# Out_current_sensor_UVW.net
KiCad netlist of a schematic drawn in Altium Designer
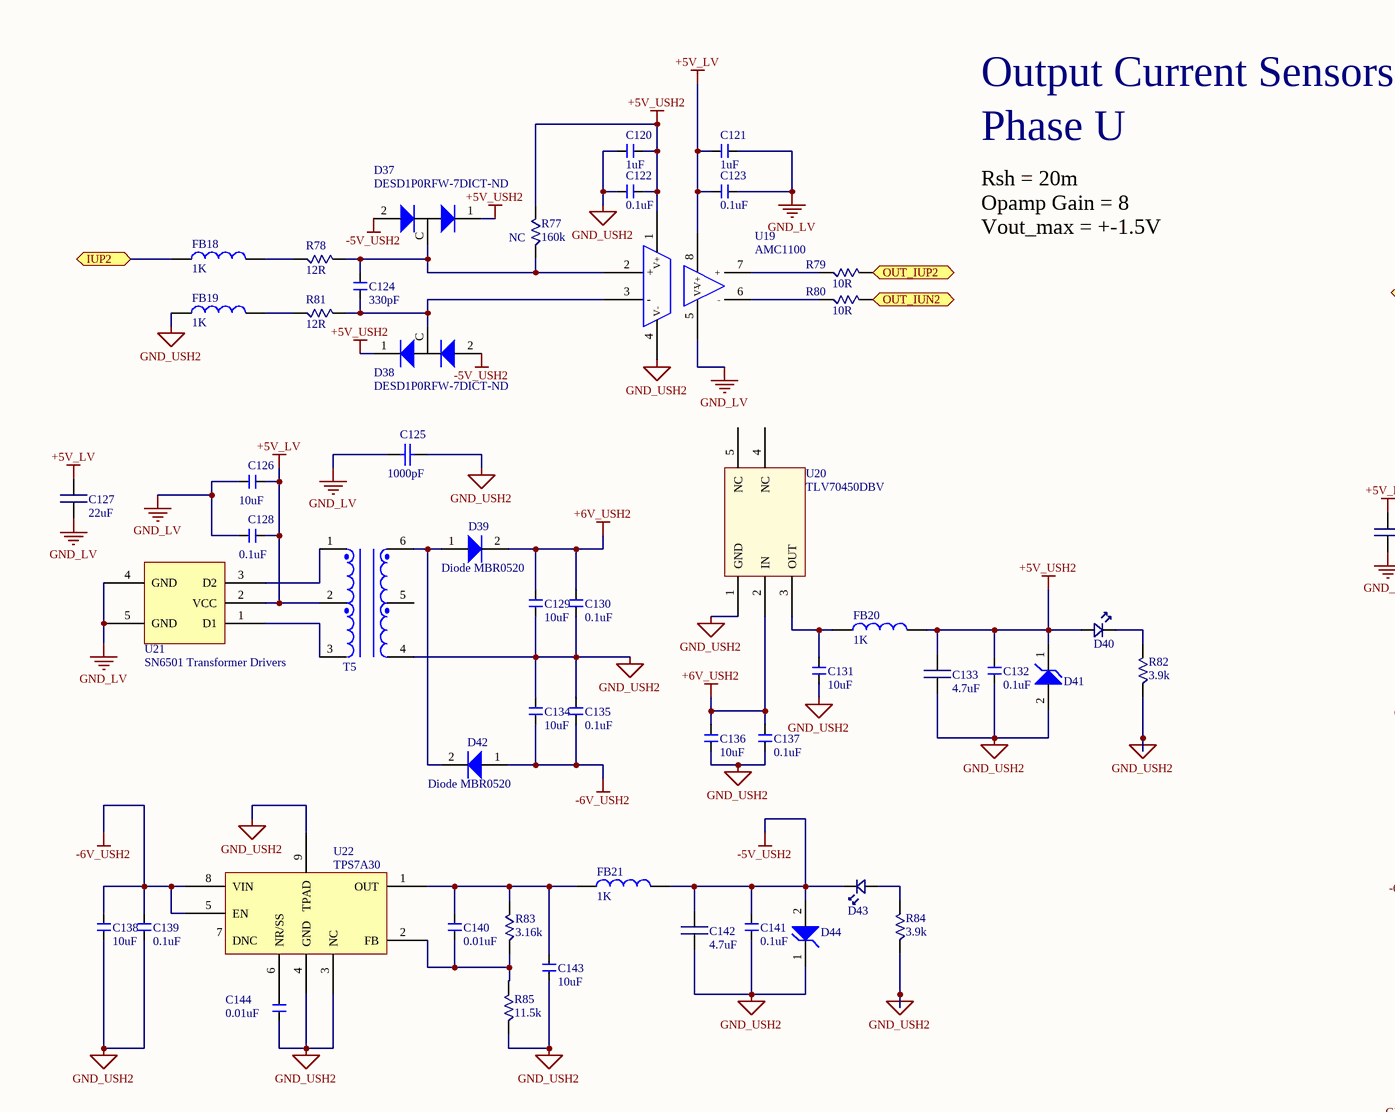
[diagram p0: Out_current_sensor_UVW.SchDoc, top left]
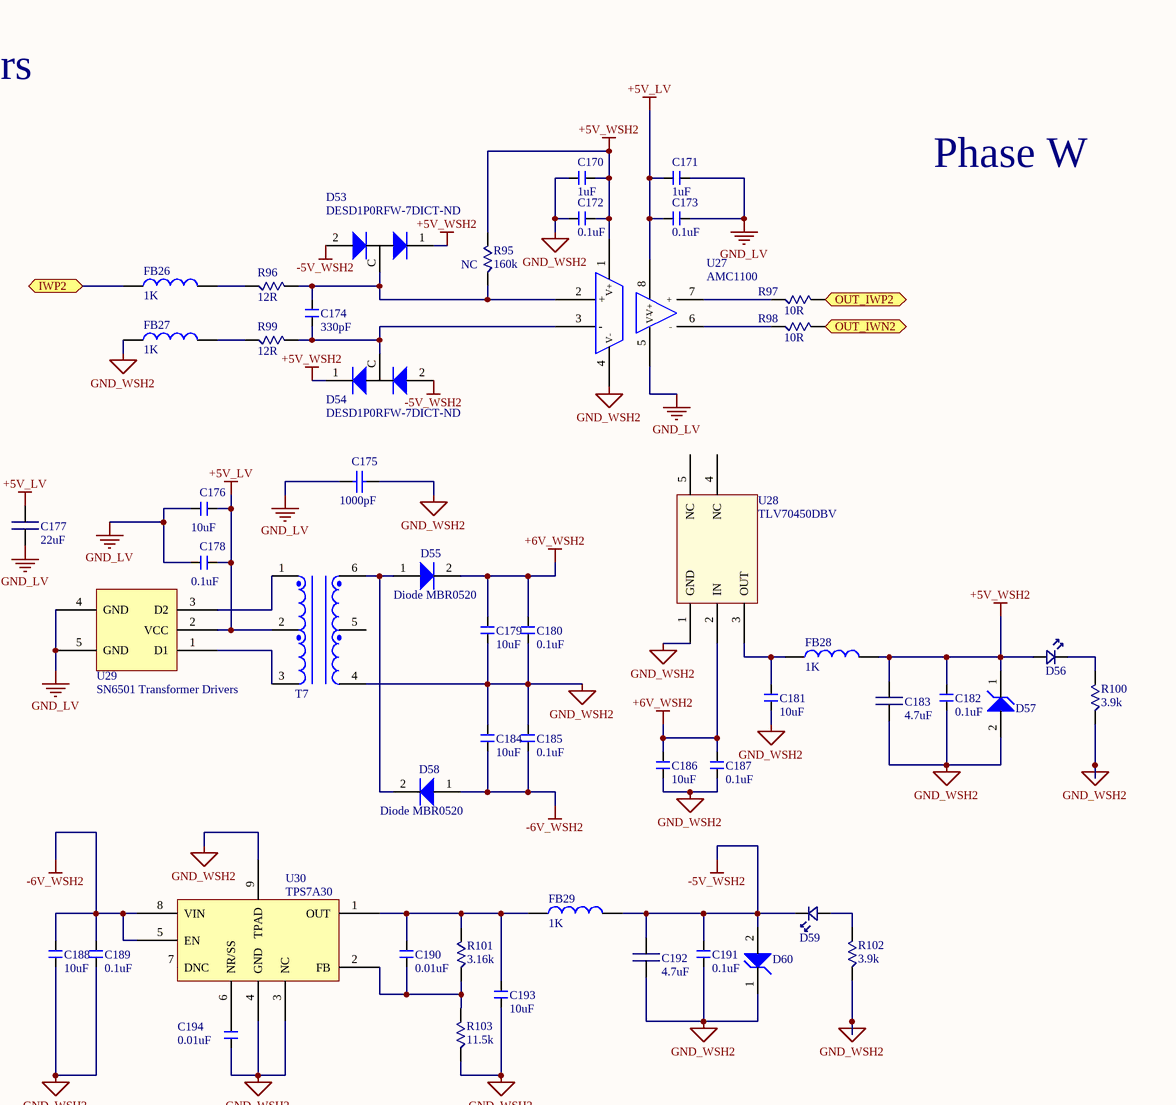
[diagram p1: Out_current_sensor_UVW.SchDoc, top right]
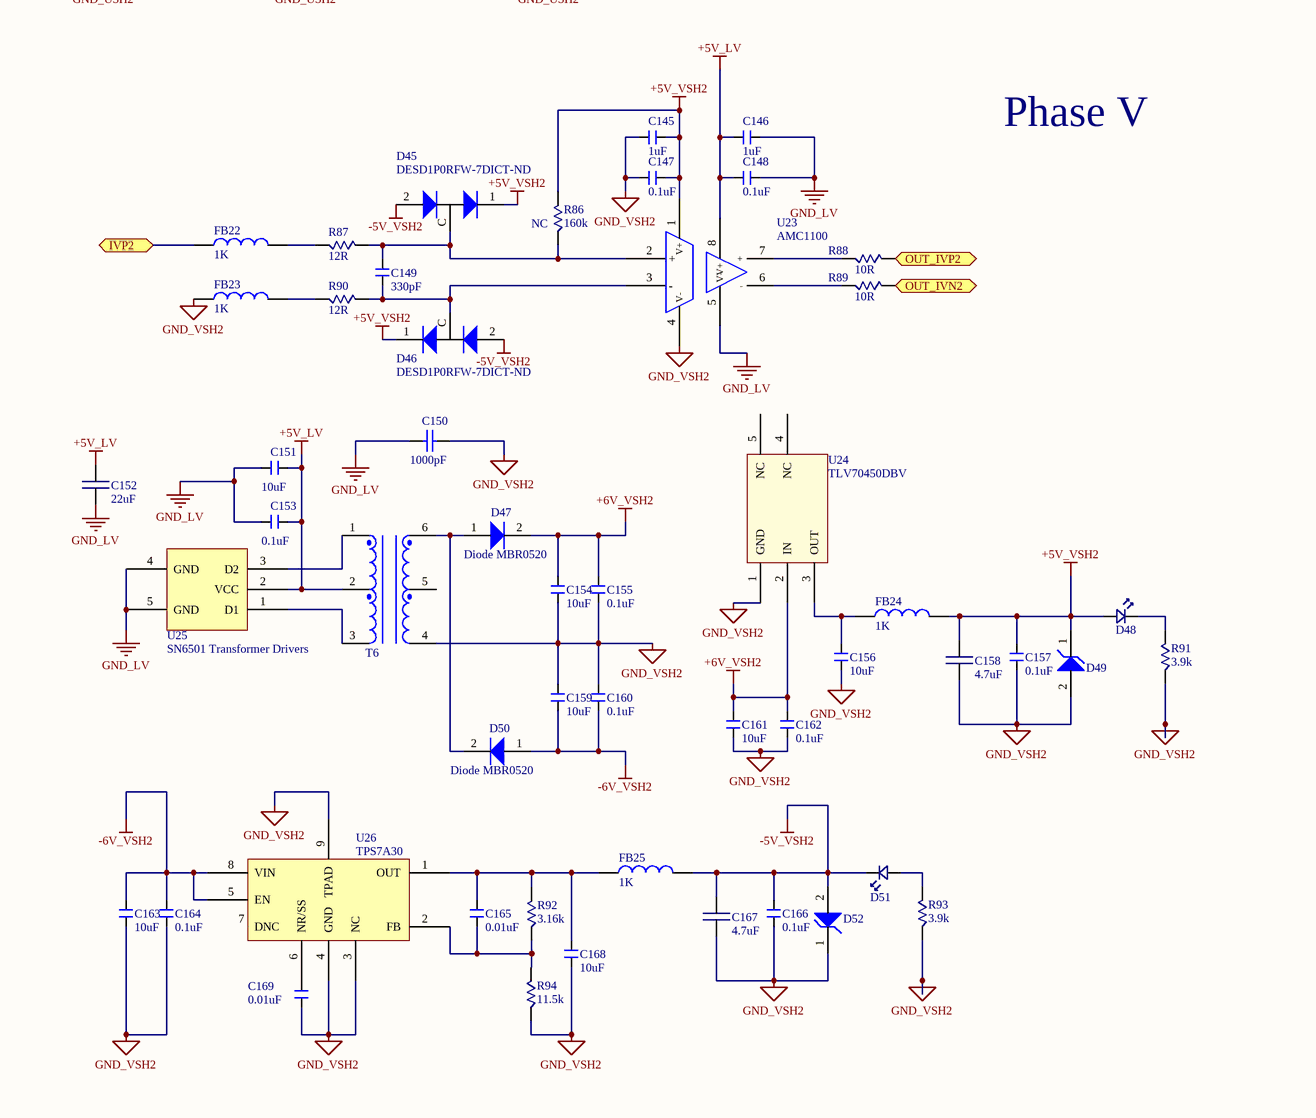
[diagram p2: Out_current_sensor_UVW.SchDoc, bottom left]

(export (version "E")
  (design (tool "Eeschema 10.0.6"))
  (components
    (comp (ref "C120")
      (value "1uF")
      (footprint "0603 (1608 Metric)")
      (description "CAP CER 1UF 50V X5R 0603")
      (fields (field (name "PART") "1276-1860-1-ND") (field (name "Comment") "Cap 0603_new"))
      (libsource (lib "Library_Microgrid") (part "Cap 0603_new"))
    )
    (comp (ref "C121")
      (value "1uF")
      (footprint "0603 (1608 Metric)")
      (description "CAP CER 1UF 50V X5R 0603")
      (fields (field (name "PART") "1276-1860-1-ND") (field (name "Comment") "Cap 0603_new"))
      (libsource (lib "Library_Microgrid") (part "Cap 0603_new"))
    )
    (comp (ref "C122")
      (value "0.1uF")
      (footprint "0603 (1608 Metric)")
      (description "CAP CER 0.1UF 50V Y5V 0603")
      (fields (field (name "PART") "311-1343-6-ND") (field (name "Comment") "Cap 0603_new"))
      (libsource (lib "Library_Microgrid") (part "Cap 0603_new"))
    )
    (comp (ref "C123")
      (value "0.1uF")
      (footprint "0603 (1608 Metric)")
      (description "CAP CER 0.1UF 50V Y5V 0603")
      (fields (field (name "PART") "311-1343-6-ND") (field (name "Comment") "Cap 0603_new"))
      (libsource (lib "Library_Microgrid") (part "Cap 0603_new"))
    )
    (comp (ref "C124")
      (value "330pF")
      (footprint "0603 (1608 Metric)")
      (description "CAP CER 330PF 50V C0G 0603")
      (fields (field (name "PART") "445-7033-2-ND") (field (name "Comment") "Cap 0603_new"))
      (libsource (lib "Library_Microgrid") (part "Cap 0603_new"))
    )
    (comp (ref "C125")
      (value "1000pF")
      (footprint "RAD-0.3")
      (description "CAP CER 1000PF 1KV Y5P RADIAL")
      (fields
        (field (name "PART") "1251PH-ND")
        (field (name "Comment") "Cap TH")
        (field (name "PUBLISHER") "Altium Limited")
      )
      (libsource (lib "Miscellaneous Devices") (part "Cap"))
    )
    (comp (ref "C126")
      (value "10uF")
      (footprint "0603 (1608 Metric)")
      (description "CAP CER 10UF 35V X5R 0805")
      (fields (field (name "PART") "490-10515-1-ND") (field (name "Comment") "Cap 0603_new"))
      (libsource (lib "Library_Microgrid") (part "Cap 0603_new"))
    )
    (comp (ref "C127")
      (value "22uF")
      (footprint "0805 (2012 metric)")
      (description "CAP CER 22UF 35V X5R 0805")
      (fields (field (name "PART") "445-14428-1-ND") (field (name "Comment") "Cap 0805"))
      (libsource (lib "Library_Microgrid") (part "Cap 0805"))
    )
    (comp (ref "C128")
      (value "0.1uF")
      (footprint "0603 (1608 Metric)")
      (description "CAP CER 0.1UF 50V Y5V 0603")
      (fields (field (name "PART") "311-1343-6-ND") (field (name "Comment") "Cap 0603_new"))
      (libsource (lib "Library_Microgrid") (part "Cap 0603_new"))
    )
    (comp (ref "C129")
      (value "10uF")
      (footprint "0603 (1608 Metric)")
      (description "CAP CER 10UF 35V X5R 0805")
      (fields (field (name "PART") "490-10515-1-ND") (field (name "Comment") "Cap 0603_new"))
      (libsource (lib "Library_Microgrid") (part "Cap 0603_new"))
    )
    (comp (ref "C130")
      (value "0.1uF")
      (footprint "0603 (1608 Metric)")
      (description "CAP CER 0.1UF 50V Y5V 0603")
      (fields (field (name "PART") "311-1343-6-ND") (field (name "Comment") "Cap 0603_new"))
      (libsource (lib "Library_Microgrid") (part "Cap 0603_new"))
    )
    (comp (ref "C131")
      (value "10uF")
      (footprint "0603 (1608 Metric)")
      (description "CAP CER 10UF 35V X5R 0805")
      (fields (field (name "PART") "490-10515-1-ND") (field (name "Comment") "Cap 0603_new"))
      (libsource (lib "Library_Microgrid") (part "Cap 0603_new"))
    )
    (comp (ref "C132")
      (value "0.1uF")
      (footprint "0603 (1608 Metric)")
      (description "CAP CER 0.1UF 50V Y5V 0603")
      (fields (field (name "PART") "311-1343-6-ND") (field (name "Comment") "Cap 0603_new"))
      (libsource (lib "Library_Microgrid") (part "Cap 0603_new"))
    )
    (comp (ref "C133")
      (value "4.7uF")
      (footprint "0805 (2012 metric)")
      (description "CAP CER 4.7UF 50V X5R 0805")
      (fields (field (name "PART") "445-5980-1-ND") (field (name "Comment") "Cap 0805"))
      (libsource (lib "Library_Microgrid") (part "Cap 0805"))
    )
    (comp (ref "C134")
      (value "10uF")
      (footprint "0603 (1608 Metric)")
      (description "CAP CER 10UF 35V X5R 0805")
      (fields (field (name "PART") "490-10515-1-ND") (field (name "Comment") "Cap 0603_new"))
      (libsource (lib "Library_Microgrid") (part "Cap 0603_new"))
    )
    (comp (ref "C135")
      (value "0.1uF")
      (footprint "0603 (1608 Metric)")
      (description "CAP CER 0.1UF 50V Y5V 0603")
      (fields (field (name "PART") "311-1343-6-ND") (field (name "Comment") "Cap 0603_new"))
      (libsource (lib "Library_Microgrid") (part "Cap 0603_new"))
    )
    (comp (ref "C136")
      (value "10uF")
      (footprint "0603 (1608 Metric)")
      (description "CAP CER 10UF 35V X5R 0805")
      (fields (field (name "PART") "490-10515-1-ND") (field (name "Comment") "Cap 0603_new"))
      (libsource (lib "Library_Microgrid") (part "Cap 0603_new"))
    )
    (comp (ref "C137")
      (value "0.1uF")
      (footprint "0603 (1608 Metric)")
      (description "CAP CER 0.1UF 50V Y5V 0603")
      (fields (field (name "PART") "311-1343-6-ND") (field (name "Comment") "Cap 0603_new"))
      (libsource (lib "Library_Microgrid") (part "Cap 0603_new"))
    )
    (comp (ref "C138")
      (value "10uF")
      (footprint "0603 (1608 Metric)")
      (description "CAP CER 10UF 35V X5R 0805")
      (fields (field (name "PART") "490-10515-1-ND") (field (name "Comment") "Cap 0603_new"))
      (libsource (lib "Library_Microgrid") (part "Cap 0603_new"))
    )
    (comp (ref "C139")
      (value "0.1uF")
      (footprint "0603 (1608 Metric)")
      (description "CAP CER 0.1UF 50V Y5V 0603")
      (fields (field (name "PART") "311-1343-6-ND") (field (name "Comment") "Cap 0603_new"))
      (libsource (lib "Library_Microgrid") (part "Cap 0603_new"))
    )
    (comp (ref "C140")
      (value "0.01uF")
      (footprint "0603 (1608 Metric)")
      (description "CAP CER 10000PF 100V X7R 0603")
      (fields (field (name "PART") "478-7418-1-ND") (field (name "Comment") "Cap 0603_new"))
      (libsource (lib "Library_Microgrid") (part "Cap 0603_new"))
    )
    (comp (ref "C141")
      (value "0.1uF")
      (footprint "0603 (1608 Metric)")
      (description "CAP CER 0.1UF 50V Y5V 0603")
      (fields (field (name "PART") "311-1343-6-ND") (field (name "Comment") "Cap 0603_new"))
      (libsource (lib "Library_Microgrid") (part "Cap 0603_new"))
    )
    (comp (ref "C142")
      (value "4.7uF")
      (footprint "0805 (2012 metric)")
      (description "CAP CER 4.7UF 50V X5R 0805")
      (fields (field (name "PART") "445-5980-1-ND") (field (name "Comment") "Cap 0805"))
      (libsource (lib "Library_Microgrid") (part "Cap 0805"))
    )
    (comp (ref "C143")
      (value "10uF")
      (footprint "0603 (1608 Metric)")
      (description "CAP CER 10UF 35V X5R 0805")
      (fields (field (name "PART") "490-10515-1-ND") (field (name "Comment") "Cap 0603_new"))
      (libsource (lib "Library_Microgrid") (part "Cap 0603_new"))
    )
    (comp (ref "C144")
      (value "0.01uF")
      (footprint "0603 (1608 Metric)")
      (description "CAP CER 10000PF 100V X7R 0603")
      (fields (field (name "PART") "478-7418-1-ND") (field (name "Comment") "Cap 0603_new"))
      (libsource (lib "Library_Microgrid") (part "Cap 0603_new"))
    )
    (comp (ref "C145")
      (value "1uF")
      (footprint "0603 (1608 Metric)")
      (description "CAP CER 1UF 50V X5R 0603")
      (fields (field (name "PART") "1276-1860-1-ND") (field (name "Comment") "Cap 0603_new"))
      (libsource (lib "Library_Microgrid") (part "Cap 0603_new"))
    )
    (comp (ref "C146")
      (value "1uF")
      (footprint "0603 (1608 Metric)")
      (description "CAP CER 1UF 50V X5R 0603")
      (fields (field (name "PART") "1276-1860-1-ND") (field (name "Comment") "Cap 0603_new"))
      (libsource (lib "Library_Microgrid") (part "Cap 0603_new"))
    )
    (comp (ref "C147")
      (value "0.1uF")
      (footprint "0603 (1608 Metric)")
      (description "CAP CER 0.1UF 50V Y5V 0603")
      (fields (field (name "PART") "311-1343-6-ND") (field (name "Comment") "Cap 0603_new"))
      (libsource (lib "Library_Microgrid") (part "Cap 0603_new"))
    )
    (comp (ref "C148")
      (value "0.1uF")
      (footprint "0603 (1608 Metric)")
      (description "CAP CER 0.1UF 50V Y5V 0603")
      (fields (field (name "PART") "311-1343-6-ND") (field (name "Comment") "Cap 0603_new"))
      (libsource (lib "Library_Microgrid") (part "Cap 0603_new"))
    )
    (comp (ref "C149")
      (value "330pF")
      (footprint "0603 (1608 Metric)")
      (description "CAP CER 330PF 50V C0G 0603")
      (fields (field (name "PART") "445-7033-2-ND") (field (name "Comment") "Cap 0603_new"))
      (libsource (lib "Library_Microgrid") (part "Cap 0603_new"))
    )
    (comp (ref "C150")
      (value "1000pF")
      (footprint "RAD-0.3")
      (description "CAP CER 1000PF 1KV Y5P RADIAL")
      (fields
        (field (name "PART") "1251PH-ND")
        (field (name "Comment") "Cap TH")
        (field (name "PUBLISHER") "Altium Limited")
      )
      (libsource (lib "Miscellaneous Devices") (part "Cap"))
    )
    (comp (ref "C151")
      (value "10uF")
      (footprint "0603 (1608 Metric)")
      (description "CAP CER 10UF 35V X5R 0805")
      (fields (field (name "PART") "490-10515-1-ND") (field (name "Comment") "Cap 0603_new"))
      (libsource (lib "Library_Microgrid") (part "Cap 0603_new"))
    )
    (comp (ref "C152")
      (value "22uF")
      (footprint "0805 (2012 metric)")
      (description "CAP CER 22UF 35V X5R 0805")
      (fields (field (name "PART") "445-14428-1-ND") (field (name "Comment") "Cap 0805"))
      (libsource (lib "Library_Microgrid") (part "Cap 0805"))
    )
    (comp (ref "C153")
      (value "0.1uF")
      (footprint "0603 (1608 Metric)")
      (description "CAP CER 0.1UF 50V Y5V 0603")
      (fields (field (name "PART") "311-1343-6-ND") (field (name "Comment") "Cap 0603_new"))
      (libsource (lib "Library_Microgrid") (part "Cap 0603_new"))
    )
    (comp (ref "C154")
      (value "10uF")
      (footprint "0603 (1608 Metric)")
      (description "CAP CER 10UF 35V X5R 0805")
      (fields (field (name "PART") "490-10515-1-ND") (field (name "Comment") "Cap 0603_new"))
      (libsource (lib "Library_Microgrid") (part "Cap 0603_new"))
    )
    (comp (ref "C155")
      (value "0.1uF")
      (footprint "0603 (1608 Metric)")
      (description "CAP CER 0.1UF 50V Y5V 0603")
      (fields (field (name "PART") "311-1343-6-ND") (field (name "Comment") "Cap 0603_new"))
      (libsource (lib "Library_Microgrid") (part "Cap 0603_new"))
    )
    (comp (ref "C156")
      (value "10uF")
      (footprint "0603 (1608 Metric)")
      (description "CAP CER 10UF 35V X5R 0805")
      (fields (field (name "PART") "490-10515-1-ND") (field (name "Comment") "Cap 0603_new"))
      (libsource (lib "Library_Microgrid") (part "Cap 0603_new"))
    )
    (comp (ref "C157")
      (value "0.1uF")
      (footprint "0603 (1608 Metric)")
      (description "CAP CER 0.1UF 50V Y5V 0603")
      (fields (field (name "PART") "311-1343-6-ND") (field (name "Comment") "Cap 0603_new"))
      (libsource (lib "Library_Microgrid") (part "Cap 0603_new"))
    )
    (comp (ref "C158")
      (value "4.7uF")
      (footprint "0805 (2012 metric)")
      (description "CAP CER 4.7UF 50V X5R 0805")
      (fields (field (name "PART") "445-5980-1-ND") (field (name "Comment") "Cap 0805"))
      (libsource (lib "Library_Microgrid") (part "Cap 0805"))
    )
    (comp (ref "C159")
      (value "10uF")
      (footprint "0603 (1608 Metric)")
      (description "CAP CER 10UF 35V X5R 0805")
      (fields (field (name "PART") "490-10515-1-ND") (field (name "Comment") "Cap 0603_new"))
      (libsource (lib "Library_Microgrid") (part "Cap 0603_new"))
    )
    (comp (ref "C160")
      (value "0.1uF")
      (footprint "0603 (1608 Metric)")
      (description "CAP CER 0.1UF 50V Y5V 0603")
      (fields (field (name "PART") "311-1343-6-ND") (field (name "Comment") "Cap 0603_new"))
      (libsource (lib "Library_Microgrid") (part "Cap 0603_new"))
    )
    (comp (ref "C161")
      (value "10uF")
      (footprint "0603 (1608 Metric)")
      (description "CAP CER 10UF 35V X5R 0805")
      (fields (field (name "PART") "490-10515-1-ND") (field (name "Comment") "Cap 0603_new"))
      (libsource (lib "Library_Microgrid") (part "Cap 0603_new"))
    )
    (comp (ref "C162")
      (value "0.1uF")
      (footprint "0603 (1608 Metric)")
      (description "CAP CER 0.1UF 50V Y5V 0603")
      (fields (field (name "PART") "311-1343-6-ND") (field (name "Comment") "Cap 0603_new"))
      (libsource (lib "Library_Microgrid") (part "Cap 0603_new"))
    )
    (comp (ref "C163")
      (value "10uF")
      (footprint "0603 (1608 Metric)")
      (description "CAP CER 10UF 35V X5R 0805")
      (fields (field (name "PART") "490-10515-1-ND") (field (name "Comment") "Cap 0603_new"))
      (libsource (lib "Library_Microgrid") (part "Cap 0603_new"))
    )
    (comp (ref "C164")
      (value "0.1uF")
      (footprint "0603 (1608 Metric)")
      (description "CAP CER 0.1UF 50V Y5V 0603")
      (fields (field (name "PART") "311-1343-6-ND") (field (name "Comment") "Cap 0603_new"))
      (libsource (lib "Library_Microgrid") (part "Cap 0603_new"))
    )
    (comp (ref "C165")
      (value "0.01uF")
      (footprint "0603 (1608 Metric)")
      (description "CAP CER 10000PF 100V X7R 0603")
      (fields (field (name "PART") "478-7418-1-ND") (field (name "Comment") "Cap 0603_new"))
      (libsource (lib "Library_Microgrid") (part "Cap 0603_new"))
    )
    (comp (ref "C166")
      (value "0.1uF")
      (footprint "0603 (1608 Metric)")
      (description "CAP CER 0.1UF 50V Y5V 0603")
      (fields (field (name "PART") "311-1343-6-ND") (field (name "Comment") "Cap 0603_new"))
      (libsource (lib "Library_Microgrid") (part "Cap 0603_new"))
    )
    (comp (ref "C167")
      (value "4.7uF")
      (footprint "0805 (2012 metric)")
      (description "CAP CER 4.7UF 50V X5R 0805")
      (fields (field (name "PART") "445-5980-1-ND") (field (name "Comment") "Cap 0805"))
      (libsource (lib "Library_Microgrid") (part "Cap 0805"))
    )
    (comp (ref "C168")
      (value "10uF")
      (footprint "0603 (1608 Metric)")
      (description "CAP CER 10UF 35V X5R 0805")
      (fields (field (name "PART") "490-10515-1-ND") (field (name "Comment") "Cap 0603_new"))
      (libsource (lib "Library_Microgrid") (part "Cap 0603_new"))
    )
    (comp (ref "C169")
      (value "0.01uF")
      (footprint "0603 (1608 Metric)")
      (description "CAP CER 10000PF 100V X7R 0603")
      (fields (field (name "PART") "478-7418-1-ND") (field (name "Comment") "Cap 0603_new"))
      (libsource (lib "Library_Microgrid") (part "Cap 0603_new"))
    )
    (comp (ref "C170")
      (value "1uF")
      (footprint "0603 (1608 Metric)")
      (description "CAP CER 1UF 50V X5R 0603")
      (fields (field (name "PART") "1276-1860-1-ND") (field (name "Comment") "Cap 0603_new"))
      (libsource (lib "Library_Microgrid") (part "Cap 0603_new"))
    )
    (comp (ref "C171")
      (value "1uF")
      (footprint "0603 (1608 Metric)")
      (description "CAP CER 1UF 50V X5R 0603")
      (fields (field (name "PART") "1276-1860-1-ND") (field (name "Comment") "Cap 0603_new"))
      (libsource (lib "Library_Microgrid") (part "Cap 0603_new"))
    )
    (comp (ref "C172")
      (value "0.1uF")
      (footprint "0603 (1608 Metric)")
      (description "CAP CER 0.1UF 50V Y5V 0603")
      (fields (field (name "PART") "311-1343-6-ND") (field (name "Comment") "Cap 0603_new"))
      (libsource (lib "Library_Microgrid") (part "Cap 0603_new"))
    )
    (comp (ref "C173")
      (value "0.1uF")
      (footprint "0603 (1608 Metric)")
      (description "CAP CER 0.1UF 50V Y5V 0603")
      (fields (field (name "PART") "311-1343-6-ND") (field (name "Comment") "Cap 0603_new"))
      (libsource (lib "Library_Microgrid") (part "Cap 0603_new"))
    )
    (comp (ref "C174")
      (value "330pF")
      (footprint "0603 (1608 Metric)")
      (description "CAP CER 330PF 50V C0G 0603")
      (fields (field (name "PART") "445-7033-2-ND") (field (name "Comment") "Cap 0603_new"))
      (libsource (lib "Library_Microgrid") (part "Cap 0603_new"))
    )
    (comp (ref "C175")
      (value "1000pF")
      (footprint "RAD-0.3")
      (description "CAP CER 1000PF 1KV Y5P RADIAL")
      (fields
        (field (name "PART") "1251PH-ND")
        (field (name "Comment") "Cap TH")
        (field (name "PUBLISHER") "Altium Limited")
      )
      (libsource (lib "Miscellaneous Devices") (part "Cap"))
    )
    (comp (ref "C176")
      (value "10uF")
      (footprint "0603 (1608 Metric)")
      (description "CAP CER 10UF 35V X5R 0805")
      (fields (field (name "PART") "490-10515-1-ND") (field (name "Comment") "Cap 0603_new"))
      (libsource (lib "Library_Microgrid") (part "Cap 0603_new"))
    )
    (comp (ref "C177")
      (value "22uF")
      (footprint "0805 (2012 metric)")
      (description "CAP CER 22UF 35V X5R 0805")
      (fields (field (name "PART") "445-14428-1-ND") (field (name "Comment") "Cap 0805"))
      (libsource (lib "Library_Microgrid") (part "Cap 0805"))
    )
    (comp (ref "C178")
      (value "0.1uF")
      (footprint "0603 (1608 Metric)")
      (description "CAP CER 0.1UF 50V Y5V 0603")
      (fields (field (name "PART") "311-1343-6-ND") (field (name "Comment") "Cap 0603_new"))
      (libsource (lib "Library_Microgrid") (part "Cap 0603_new"))
    )
    (comp (ref "C179")
      (value "10uF")
      (footprint "0603 (1608 Metric)")
      (description "CAP CER 10UF 35V X5R 0805")
      (fields (field (name "PART") "490-10515-1-ND") (field (name "Comment") "Cap 0603_new"))
      (libsource (lib "Library_Microgrid") (part "Cap 0603_new"))
    )
    (comp (ref "C180")
      (value "0.1uF")
      (footprint "0603 (1608 Metric)")
      (description "CAP CER 0.1UF 50V Y5V 0603")
      (fields (field (name "PART") "311-1343-6-ND") (field (name "Comment") "Cap 0603_new"))
      (libsource (lib "Library_Microgrid") (part "Cap 0603_new"))
    )
    (comp (ref "C181")
      (value "10uF")
      (footprint "0603 (1608 Metric)")
      (description "CAP CER 10UF 35V X5R 0805")
      (fields (field (name "PART") "490-10515-1-ND") (field (name "Comment") "Cap 0603_new"))
      (libsource (lib "Library_Microgrid") (part "Cap 0603_new"))
    )
    (comp (ref "C182")
      (value "0.1uF")
      (footprint "0603 (1608 Metric)")
      (description "CAP CER 0.1UF 50V Y5V 0603")
      (fields (field (name "PART") "311-1343-6-ND") (field (name "Comment") "Cap 0603_new"))
      (libsource (lib "Library_Microgrid") (part "Cap 0603_new"))
    )
    (comp (ref "C183")
      (value "4.7uF")
      (footprint "0805 (2012 metric)")
      (description "CAP CER 4.7UF 50V X5R 0805")
      (fields (field (name "PART") "445-5980-1-ND") (field (name "Comment") "Cap 0805"))
      (libsource (lib "Library_Microgrid") (part "Cap 0805"))
    )
    (comp (ref "C184")
      (value "10uF")
      (footprint "0603 (1608 Metric)")
      (description "CAP CER 10UF 35V X5R 0805")
      (fields (field (name "PART") "490-10515-1-ND") (field (name "Comment") "Cap 0603_new"))
      (libsource (lib "Library_Microgrid") (part "Cap 0603_new"))
    )
    (comp (ref "C185")
      (value "0.1uF")
      (footprint "0603 (1608 Metric)")
      (description "CAP CER 0.1UF 50V Y5V 0603")
      (fields (field (name "PART") "311-1343-6-ND") (field (name "Comment") "Cap 0603_new"))
      (libsource (lib "Library_Microgrid") (part "Cap 0603_new"))
    )
    (comp (ref "C186")
      (value "10uF")
      (footprint "0603 (1608 Metric)")
      (description "CAP CER 10UF 35V X5R 0805")
      (fields (field (name "PART") "490-10515-1-ND") (field (name "Comment") "Cap 0603_new"))
      (libsource (lib "Library_Microgrid") (part "Cap 0603_new"))
    )
    (comp (ref "C187")
      (value "0.1uF")
      (footprint "0603 (1608 Metric)")
      (description "CAP CER 0.1UF 50V Y5V 0603")
      (fields (field (name "PART") "311-1343-6-ND") (field (name "Comment") "Cap 0603_new"))
      (libsource (lib "Library_Microgrid") (part "Cap 0603_new"))
    )
    (comp (ref "C188")
      (value "10uF")
      (footprint "0603 (1608 Metric)")
      (description "CAP CER 10UF 35V X5R 0805")
      (fields (field (name "PART") "490-10515-1-ND") (field (name "Comment") "Cap 0603_new"))
      (libsource (lib "Library_Microgrid") (part "Cap 0603_new"))
    )
    (comp (ref "C189")
      (value "0.1uF")
      (footprint "0603 (1608 Metric)")
      (description "CAP CER 0.1UF 50V Y5V 0603")
      (fields (field (name "PART") "311-1343-6-ND") (field (name "Comment") "Cap 0603_new"))
      (libsource (lib "Library_Microgrid") (part "Cap 0603_new"))
    )
    (comp (ref "C190")
      (value "0.01uF")
      (footprint "0603 (1608 Metric)")
      (description "CAP CER 10000PF 100V X7R 0603")
      (fields (field (name "PART") "478-7418-1-ND") (field (name "Comment") "Cap 0603_new"))
      (libsource (lib "Library_Microgrid") (part "Cap 0603_new"))
    )
    (comp (ref "C191")
      (value "0.1uF")
      (footprint "0603 (1608 Metric)")
      (description "CAP CER 0.1UF 50V Y5V 0603")
      (fields (field (name "PART") "311-1343-6-ND") (field (name "Comment") "Cap 0603_new"))
      (libsource (lib "Library_Microgrid") (part "Cap 0603_new"))
    )
    (comp (ref "C192")
      (value "4.7uF")
      (footprint "0805 (2012 metric)")
      (description "CAP CER 4.7UF 50V X5R 0805")
      (fields (field (name "PART") "445-5980-1-ND") (field (name "Comment") "Cap 0805"))
      (libsource (lib "Library_Microgrid") (part "Cap 0805"))
    )
    (comp (ref "C193")
      (value "10uF")
      (footprint "0603 (1608 Metric)")
      (description "CAP CER 10UF 35V X5R 0805")
      (fields (field (name "PART") "490-10515-1-ND") (field (name "Comment") "Cap 0603_new"))
      (libsource (lib "Library_Microgrid") (part "Cap 0603_new"))
    )
    (comp (ref "C194")
      (value "0.01uF")
      (footprint "0603 (1608 Metric)")
      (description "CAP CER 10000PF 100V X7R 0603")
      (fields (field (name "PART") "478-7418-1-ND") (field (name "Comment") "Cap 0603_new"))
      (libsource (lib "Library_Microgrid") (part "Cap 0603_new"))
    )
    (comp (ref "D37")
      (value "TVS - Diodes")
      (footprint "SOT323_ESD")
      (description "TVS DIODE 70VWM 8VC SOT323")
      (fields (field (name "PART") "DESD1P0RFW-7DICT-ND"))
      (libsource (lib "Library_Microgrid") (part "Diode_ESD"))
    )
    (comp (ref "D38")
      (value "TVS - Diodes")
      (footprint "SOT323_ESD")
      (description "TVS DIODE 70VWM 8VC SOT323")
      (fields (field (name "PART") "DESD1P0RFW-7DICT-ND"))
      (libsource (lib "Library_Microgrid") (part "Diode_ESD"))
    )
    (comp (ref "D39")
      (value "Diode MBR0520")
      (footprint "SOD-123")
      (description "DIODE SCHOTTKY 20V 500MA SOD123")
      (fields (field (name "PART") "MBR0520LT1GOSCT-ND"))
      (libsource (lib "Library_Microgrid") (part "Diode MBR0520"))
    )
    (comp (ref "D40")
      (value "LED")
      (footprint "0805 (2012 Metric) Diode")
      (description "LED 0805")
      (libsource (lib "Library_Microgrid") (part "LED"))
    )
    (comp (ref "D41")
      (value "*")
      (footprint "POWERDI")
      (description "DIODE ZENER POWERDI123")
      (fields (field (name "PART") "MMSZ5228B-FDICT-ND"))
      (libsource (lib "Library_Microgrid") (part "Diode Zener POWERDI123"))
    )
    (comp (ref "D42")
      (value "Diode MBR0520")
      (footprint "SOD-123")
      (description "DIODE SCHOTTKY 20V 500MA SOD123")
      (fields (field (name "PART") "MBR0520LT1GOSCT-ND"))
      (libsource (lib "Library_Microgrid") (part "Diode MBR0520"))
    )
    (comp (ref "D43")
      (value "LED")
      (footprint "0805 (2012 Metric) Diode")
      (description "LED 0805")
      (libsource (lib "Library_Microgrid") (part "LED"))
    )
    (comp (ref "D44")
      (value "*")
      (footprint "POWERDI")
      (description "DIODE ZENER POWERDI123")
      (fields (field (name "PART") "MMSZ5228B-FDICT-ND"))
      (libsource (lib "Library_Microgrid") (part "Diode Zener POWERDI123"))
    )
    (comp (ref "D45")
      (value "TVS - Diodes")
      (footprint "SOT323_ESD")
      (description "TVS DIODE 70VWM 8VC SOT323")
      (fields (field (name "PART") "DESD1P0RFW-7DICT-ND"))
      (libsource (lib "Library_Microgrid") (part "Diode_ESD"))
    )
    (comp (ref "D46")
      (value "TVS - Diodes")
      (footprint "SOT323_ESD")
      (description "TVS DIODE 70VWM 8VC SOT323")
      (fields (field (name "PART") "DESD1P0RFW-7DICT-ND"))
      (libsource (lib "Library_Microgrid") (part "Diode_ESD"))
    )
    (comp (ref "D47")
      (value "Diode MBR0520")
      (footprint "SOD-123")
      (description "DIODE SCHOTTKY 20V 500MA SOD123")
      (fields (field (name "PART") "MBR0520LT1GOSCT-ND"))
      (libsource (lib "Library_Microgrid") (part "Diode MBR0520"))
    )
    (comp (ref "D48")
      (value "LED")
      (footprint "0805 (2012 Metric) Diode")
      (description "LED 0805")
      (libsource (lib "Library_Microgrid") (part "LED"))
    )
    (comp (ref "D49")
      (value "*")
      (footprint "POWERDI")
      (description "DIODE ZENER POWERDI123")
      (fields (field (name "PART") "MMSZ5228B-FDICT-ND"))
      (libsource (lib "Library_Microgrid") (part "Diode Zener POWERDI123"))
    )
    (comp (ref "D50")
      (value "Diode MBR0520")
      (footprint "SOD-123")
      (description "DIODE SCHOTTKY 20V 500MA SOD123")
      (fields (field (name "PART") "MBR0520LT1GOSCT-ND"))
      (libsource (lib "Library_Microgrid") (part "Diode MBR0520"))
    )
    (comp (ref "D51")
      (value "LED")
      (footprint "0805 (2012 Metric) Diode")
      (description "LED 0805")
      (libsource (lib "Library_Microgrid") (part "LED"))
    )
    (comp (ref "D52")
      (value "*")
      (footprint "POWERDI")
      (description "DIODE ZENER POWERDI123")
      (fields (field (name "PART") "MMSZ5228B-FDICT-ND"))
      (libsource (lib "Library_Microgrid") (part "Diode Zener POWERDI123"))
    )
    (comp (ref "D53")
      (value "TVS - Diodes")
      (footprint "SOT323_ESD")
      (description "TVS DIODE 70VWM 8VC SOT323")
      (fields (field (name "PART") "DESD1P0RFW-7DICT-ND"))
      (libsource (lib "Library_Microgrid") (part "Diode_ESD"))
    )
    (comp (ref "D54")
      (value "TVS - Diodes")
      (footprint "SOT323_ESD")
      (description "TVS DIODE 70VWM 8VC SOT323")
      (fields (field (name "PART") "DESD1P0RFW-7DICT-ND"))
      (libsource (lib "Library_Microgrid") (part "Diode_ESD"))
    )
    (comp (ref "D55")
      (value "Diode MBR0520")
      (footprint "SOD-123")
      (description "DIODE SCHOTTKY 20V 500MA SOD123")
      (fields (field (name "PART") "MBR0520LT1GOSCT-ND"))
      (libsource (lib "Library_Microgrid") (part "Diode MBR0520"))
    )
    (comp (ref "D56")
      (value "LED")
      (footprint "0805 (2012 Metric) Diode")
      (description "LED 0805")
      (libsource (lib "Library_Microgrid") (part "LED"))
    )
    (comp (ref "D57")
      (value "*")
      (footprint "POWERDI")
      (description "DIODE ZENER POWERDI123")
      (fields (field (name "PART") "MMSZ5228B-FDICT-ND"))
      (libsource (lib "Library_Microgrid") (part "Diode Zener POWERDI123"))
    )
    (comp (ref "D58")
      (value "Diode MBR0520")
      (footprint "SOD-123")
      (description "DIODE SCHOTTKY 20V 500MA SOD123")
      (fields (field (name "PART") "MBR0520LT1GOSCT-ND"))
      (libsource (lib "Library_Microgrid") (part "Diode MBR0520"))
    )
    (comp (ref "D59")
      (value "LED")
      (footprint "0805 (2012 Metric) Diode")
      (description "LED 0805")
      (libsource (lib "Library_Microgrid") (part "LED"))
    )
    (comp (ref "D60")
      (value "*")
      (footprint "POWERDI")
      (description "DIODE ZENER POWERDI123")
      (fields (field (name "PART") "MMSZ5228B-FDICT-ND"))
      (libsource (lib "Library_Microgrid") (part "Diode Zener POWERDI123"))
    )
    (comp (ref "FB18")
      (value "1K")
      (footprint "0603 (1608 Metric)")
      (description "FERRITE BEAD 1 KOHM 0603 1LN")
      (fields (field (name "PART") "445-8672-1-ND") (field (name "Comment") "Ferrite bead"))
      (libsource (lib "Library_Microgrid") (part "Ferrite bead"))
    )
    (comp (ref "FB19")
      (value "1K")
      (footprint "0603 (1608 Metric)")
      (description "FERRITE BEAD 1 KOHM 0603 1LN")
      (fields (field (name "PART") "445-8672-1-ND") (field (name "Comment") "Ferrite bead"))
      (libsource (lib "Library_Microgrid") (part "Ferrite bead"))
    )
    (comp (ref "FB20")
      (value "1K")
      (footprint "0603 (1608 Metric)")
      (description "FERRITE BEAD 1 KOHM 0603 1LN")
      (fields (field (name "PART") "445-8672-1-ND") (field (name "Comment") "Ferrite bead"))
      (libsource (lib "Library_Microgrid") (part "Ferrite bead"))
    )
    (comp (ref "FB21")
      (value "1K")
      (footprint "0603 (1608 Metric)")
      (description "FERRITE BEAD 1 KOHM 0603 1LN")
      (fields (field (name "PART") "445-8672-1-ND") (field (name "Comment") "Ferrite bead"))
      (libsource (lib "Library_Microgrid") (part "Ferrite bead"))
    )
    (comp (ref "FB22")
      (value "1K")
      (footprint "0603 (1608 Metric)")
      (description "FERRITE BEAD 1 KOHM 0603 1LN")
      (fields (field (name "PART") "445-8672-1-ND") (field (name "Comment") "Ferrite bead"))
      (libsource (lib "Library_Microgrid") (part "Ferrite bead"))
    )
    (comp (ref "FB23")
      (value "1K")
      (footprint "0603 (1608 Metric)")
      (description "FERRITE BEAD 1 KOHM 0603 1LN")
      (fields (field (name "PART") "445-8672-1-ND") (field (name "Comment") "Ferrite bead"))
      (libsource (lib "Library_Microgrid") (part "Ferrite bead"))
    )
    (comp (ref "FB24")
      (value "1K")
      (footprint "0603 (1608 Metric)")
      (description "FERRITE BEAD 1 KOHM 0603 1LN")
      (fields (field (name "PART") "445-8672-1-ND") (field (name "Comment") "Ferrite bead"))
      (libsource (lib "Library_Microgrid") (part "Ferrite bead"))
    )
    (comp (ref "FB25")
      (value "1K")
      (footprint "0603 (1608 Metric)")
      (description "FERRITE BEAD 1 KOHM 0603 1LN")
      (fields (field (name "PART") "445-8672-1-ND") (field (name "Comment") "Ferrite bead"))
      (libsource (lib "Library_Microgrid") (part "Ferrite bead"))
    )
    (comp (ref "FB26")
      (value "1K")
      (footprint "0603 (1608 Metric)")
      (description "FERRITE BEAD 1 KOHM 0603 1LN")
      (fields (field (name "PART") "445-8672-1-ND") (field (name "Comment") "Ferrite bead"))
      (libsource (lib "Library_Microgrid") (part "Ferrite bead"))
    )
    (comp (ref "FB27")
      (value "1K")
      (footprint "0603 (1608 Metric)")
      (description "FERRITE BEAD 1 KOHM 0603 1LN")
      (fields (field (name "PART") "445-8672-1-ND") (field (name "Comment") "Ferrite bead"))
      (libsource (lib "Library_Microgrid") (part "Ferrite bead"))
    )
    (comp (ref "FB28")
      (value "1K")
      (footprint "0603 (1608 Metric)")
      (description "FERRITE BEAD 1 KOHM 0603 1LN")
      (fields (field (name "PART") "445-8672-1-ND") (field (name "Comment") "Ferrite bead"))
      (libsource (lib "Library_Microgrid") (part "Ferrite bead"))
    )
    (comp (ref "FB29")
      (value "1K")
      (footprint "0603 (1608 Metric)")
      (description "FERRITE BEAD 1 KOHM 0603 1LN")
      (fields (field (name "PART") "445-8672-1-ND") (field (name "Comment") "Ferrite bead"))
      (libsource (lib "Library_Microgrid") (part "Ferrite bead"))
    )
    (comp (ref "R77")
      (value "NC")
      (footprint "0603 (1608 Metric)")
      (description "Resistor 0603")
      (fields (field (name "ALTIUM_VALUE") "160k"))
      (libsource (lib "Library_Microgrid") (part "Resistor 0603"))
    )
    (comp (ref "R78")
      (value "12R")
      (footprint "1206")
      (description "12 Ohm ±0.5% 0.25W, 1/4W Chip Resistor 1206")
      (fields (field (name "PART") "311-2961-1-ND") (field (name "Comment") "Resistor 1206"))
      (libsource (lib "Library_Microgrid") (part "Resistor 1206"))
    )
    (comp (ref "R79")
      (value "10R")
      (footprint "0603 (1608 Metric)")
      (description "RES SMD 10 OHM 0.05% 1/10W 0603")
      (fields (field (name "PART") "RNCF0603AKT10R0CT-ND") (field (name "Comment") "Resistor 0603"))
      (libsource (lib "Library_Microgrid") (part "Resistor 0603"))
    )
    (comp (ref "R80")
      (value "10R")
      (footprint "0603 (1608 Metric)")
      (description "RES SMD 10 OHM 0.05% 1/10W 0603")
      (fields (field (name "PART") "RNCF0603AKT10R0CT-ND") (field (name "Comment") "Resistor 0603"))
      (libsource (lib "Library_Microgrid") (part "Resistor 0603"))
    )
    (comp (ref "R81")
      (value "12R")
      (footprint "1206")
      (description "12 Ohm ±0.5% 0.25W, 1/4W Chip Resistor 1206")
      (fields (field (name "PART") "311-2961-1-ND") (field (name "Comment") "Resistor 1206"))
      (libsource (lib "Library_Microgrid") (part "Resistor 1206"))
    )
    (comp (ref "R82")
      (value "3.9k")
      (footprint "0603 (1608 Metric)")
      (description "RES SMD 3.9K OHM 5% 1/10W 0603")
      (fields (field (name "PART") "541-3.9KGCT-ND") (field (name "Comment") "Resistor 0603"))
      (libsource (lib "Library_Microgrid") (part "Resistor 0603"))
    )
    (comp (ref "R83")
      (value "3.16k")
      (footprint "0603 (1608 Metric)")
      (description "RES SMD 3.16K OHM 1% 1/10W 0603")
      (fields (field (name "PART") "311-3.16KHRCT-ND") (field (name "Comment") "Resistor 0603"))
      (libsource (lib "Library_Microgrid") (part "Resistor 0603"))
    )
    (comp (ref "R84")
      (value "3.9k")
      (footprint "0603 (1608 Metric)")
      (description "RES SMD 3.9K OHM 5% 1/10W 0603")
      (fields (field (name "PART") "541-3.9KGCT-ND") (field (name "Comment") "Resistor 0603"))
      (libsource (lib "Library_Microgrid") (part "Resistor 0603"))
    )
    (comp (ref "R85")
      (value "11.5k")
      (footprint "0603 (1608 Metric)")
      (description "RES SMD 11.5K OHM 1% 1/10W 0603")
      (fields (field (name "PART") "541-11.5KHCT-ND") (field (name "Comment") "Resistor 0603"))
      (libsource (lib "Library_Microgrid") (part "Resistor 0603"))
    )
    (comp (ref "R86")
      (value "NC")
      (footprint "0603 (1608 Metric)")
      (description "Resistor 0603")
      (fields (field (name "ALTIUM_VALUE") "160k"))
      (libsource (lib "Library_Microgrid") (part "Resistor 0603"))
    )
    (comp (ref "R87")
      (value "12R")
      (footprint "1206")
      (description "12 Ohm ±0.5% 0.25W, 1/4W Chip Resistor 1206")
      (fields (field (name "PART") "311-2961-1-ND") (field (name "Comment") "Resistor 1206"))
      (libsource (lib "Library_Microgrid") (part "Resistor 1206"))
    )
    (comp (ref "R88")
      (value "10R")
      (footprint "0603 (1608 Metric)")
      (description "RES SMD 10 OHM 0.05% 1/10W 0603")
      (fields (field (name "PART") "RNCF0603AKT10R0CT-ND") (field (name "Comment") "Resistor 0603"))
      (libsource (lib "Library_Microgrid") (part "Resistor 0603"))
    )
    (comp (ref "R89")
      (value "10R")
      (footprint "0603 (1608 Metric)")
      (description "RES SMD 10 OHM 0.05% 1/10W 0603")
      (fields (field (name "PART") "RNCF0603AKT10R0CT-ND") (field (name "Comment") "Resistor 0603"))
      (libsource (lib "Library_Microgrid") (part "Resistor 0603"))
    )
    (comp (ref "R90")
      (value "12R")
      (footprint "1206")
      (description "12 Ohm ±0.5% 0.25W, 1/4W Chip Resistor 1206")
      (fields (field (name "PART") "311-2961-1-ND") (field (name "Comment") "Resistor 1206"))
      (libsource (lib "Library_Microgrid") (part "Resistor 1206"))
    )
    (comp (ref "R91")
      (value "3.9k")
      (footprint "0603 (1608 Metric)")
      (description "RES SMD 3.9K OHM 5% 1/10W 0603")
      (fields (field (name "PART") "541-3.9KGCT-ND") (field (name "Comment") "Resistor 0603"))
      (libsource (lib "Library_Microgrid") (part "Resistor 0603"))
    )
    (comp (ref "R92")
      (value "3.16k")
      (footprint "0603 (1608 Metric)")
      (description "RES SMD 3.16K OHM 1% 1/10W 0603")
      (fields (field (name "PART") "311-3.16KHRCT-ND") (field (name "Comment") "Resistor 0603"))
      (libsource (lib "Library_Microgrid") (part "Resistor 0603"))
    )
    (comp (ref "R93")
      (value "3.9k")
      (footprint "0603 (1608 Metric)")
      (description "RES SMD 3.9K OHM 5% 1/10W 0603")
      (fields (field (name "PART") "541-3.9KGCT-ND") (field (name "Comment") "Resistor 0603"))
      (libsource (lib "Library_Microgrid") (part "Resistor 0603"))
    )
    (comp (ref "R94")
      (value "11.5k")
      (footprint "0603 (1608 Metric)")
      (description "RES SMD 11.5K OHM 1% 1/10W 0603")
      (fields (field (name "PART") "541-11.5KHCT-ND") (field (name "Comment") "Resistor 0603"))
      (libsource (lib "Library_Microgrid") (part "Resistor 0603"))
    )
    (comp (ref "R95")
      (value "NC")
      (footprint "0603 (1608 Metric)")
      (description "Resistor 0603")
      (fields (field (name "ALTIUM_VALUE") "160k"))
      (libsource (lib "Library_Microgrid") (part "Resistor 0603"))
    )
    (comp (ref "R96")
      (value "12R")
      (footprint "1206")
      (description "12 Ohm ±0.5% 0.25W, 1/4W Chip Resistor 1206")
      (fields (field (name "PART") "311-2961-1-ND") (field (name "Comment") "Resistor 1206"))
      (libsource (lib "Library_Microgrid") (part "Resistor 1206"))
    )
    (comp (ref "R97")
      (value "10R")
      (footprint "0603 (1608 Metric)")
      (description "RES SMD 10 OHM 0.05% 1/10W 0603")
      (fields (field (name "PART") "RNCF0603AKT10R0CT-ND") (field (name "Comment") "Resistor 0603"))
      (libsource (lib "Library_Microgrid") (part "Resistor 0603"))
    )
    (comp (ref "R98")
      (value "10R")
      (footprint "0603 (1608 Metric)")
      (description "RES SMD 10 OHM 0.05% 1/10W 0603")
      (fields (field (name "PART") "RNCF0603AKT10R0CT-ND") (field (name "Comment") "Resistor 0603"))
      (libsource (lib "Library_Microgrid") (part "Resistor 0603"))
    )
    (comp (ref "R99")
      (value "12R")
      (footprint "1206")
      (description "12 Ohm ±0.5% 0.25W, 1/4W Chip Resistor 1206")
      (fields (field (name "PART") "311-2961-1-ND") (field (name "Comment") "Resistor 1206"))
      (libsource (lib "Library_Microgrid") (part "Resistor 1206"))
    )
    (comp (ref "R100")
      (value "3.9k")
      (footprint "0603 (1608 Metric)")
      (description "RES SMD 3.9K OHM 5% 1/10W 0603")
      (fields (field (name "PART") "541-3.9KGCT-ND") (field (name "Comment") "Resistor 0603"))
      (libsource (lib "Library_Microgrid") (part "Resistor 0603"))
    )
    (comp (ref "R101")
      (value "3.16k")
      (footprint "0603 (1608 Metric)")
      (description "RES SMD 3.16K OHM 1% 1/10W 0603")
      (fields (field (name "PART") "311-3.16KHRCT-ND") (field (name "Comment") "Resistor 0603"))
      (libsource (lib "Library_Microgrid") (part "Resistor 0603"))
    )
    (comp (ref "R102")
      (value "3.9k")
      (footprint "0603 (1608 Metric)")
      (description "RES SMD 3.9K OHM 5% 1/10W 0603")
      (fields (field (name "PART") "541-3.9KGCT-ND") (field (name "Comment") "Resistor 0603"))
      (libsource (lib "Library_Microgrid") (part "Resistor 0603"))
    )
    (comp (ref "R103")
      (value "11.5k")
      (footprint "0603 (1608 Metric)")
      (description "RES SMD 11.5K OHM 1% 1/10W 0603")
      (fields (field (name "PART") "541-11.5KHCT-ND") (field (name "Comment") "Resistor 0603"))
      (libsource (lib "Library_Microgrid") (part "Resistor 0603"))
    )
    (comp (ref "T5")
      (value "750313769")
      (footprint "Xmr SN6501")
      (description "TRANSFORMER SMD TR1.7 SN6501")
      (fields (field (name "PART") "1297-1107-1-ND"))
      (libsource (lib "Library_Microgrid") (part "750313769"))
    )
    (comp (ref "T6")
      (value "750313769")
      (footprint "Xmr SN6501")
      (description "TRANSFORMER SMD TR1.7 SN6501")
      (fields (field (name "PART") "1297-1107-1-ND"))
      (libsource (lib "Library_Microgrid") (part "750313769"))
    )
    (comp (ref "T7")
      (value "750313769")
      (footprint "Xmr SN6501")
      (description "TRANSFORMER SMD TR1.7 SN6501")
      (fields (field (name "PART") "1297-1107-1-ND"))
      (libsource (lib "Library_Microgrid") (part "750313769"))
    )
    (comp (ref "U19")
      (value "AMC1100")
      (footprint "SOIC8")
      (description "IC OPAMP ISOLATION 100KHZ 8SOIC")
      (fields (field (name "PART") "296-38822-5-ND"))
      (libsource (lib "Library_Microgrid") (part "AMC1100"))
    )
    (comp (ref "U20")
      (value "TLV70450DBV")
      (footprint "SOT23-5")
      (description "IC REG LDO 5V 0.15A SOT23-5")
      (fields (field (name "PART") "296-39287-1-ND"))
      (libsource (lib "Library_Microgrid") (part "TLV70450DBV"))
    )
    (comp (ref "U21")
      (value "SN6501 Transformer Drivers")
      (footprint "SOT23-5")
      (description "IC REG CONV PWR SUPPLIES SOT23-5")
      (fields (field (name "PART") "296-37700-1-ND"))
      (libsource (lib "Library_Microgrid") (part "SN6501"))
    )
    (comp (ref "U22")
      (value "TPS7A30")
      (footprint "8-TSSOP")
      (description "IC REG LDO NEG ADJ 0.2A 8MSOP")
      (fields (field (name "PART") "296-27750-1-ND"))
      (libsource (lib "Library_Microgrid") (part "TPS7A30"))
    )
    (comp (ref "U23")
      (value "AMC1100")
      (footprint "SOIC8")
      (description "IC OPAMP ISOLATION 100KHZ 8SOIC")
      (fields (field (name "PART") "296-38822-5-ND"))
      (libsource (lib "Library_Microgrid") (part "AMC1100"))
    )
    (comp (ref "U24")
      (value "TLV70450DBV")
      (footprint "SOT23-5")
      (description "IC REG LDO 5V 0.15A SOT23-5")
      (fields (field (name "PART") "296-39287-1-ND"))
      (libsource (lib "Library_Microgrid") (part "TLV70450DBV"))
    )
    (comp (ref "U25")
      (value "SN6501 Transformer Drivers")
      (footprint "SOT23-5")
      (description "IC REG CONV PWR SUPPLIES SOT23-5")
      (fields (field (name "PART") "296-37700-1-ND"))
      (libsource (lib "Library_Microgrid") (part "SN6501"))
    )
    (comp (ref "U26")
      (value "TPS7A30")
      (footprint "8-TSSOP")
      (description "IC REG LDO NEG ADJ 0.2A 8MSOP")
      (fields (field (name "PART") "296-27750-1-ND"))
      (libsource (lib "Library_Microgrid") (part "TPS7A30"))
    )
    (comp (ref "U27")
      (value "AMC1100")
      (footprint "SOIC8")
      (description "IC OPAMP ISOLATION 100KHZ 8SOIC")
      (fields (field (name "PART") "296-38822-5-ND"))
      (libsource (lib "Library_Microgrid") (part "AMC1100"))
    )
    (comp (ref "U28")
      (value "TLV70450DBV")
      (footprint "SOT23-5")
      (description "IC REG LDO 5V 0.15A SOT23-5")
      (fields (field (name "PART") "296-39287-1-ND"))
      (libsource (lib "Library_Microgrid") (part "TLV70450DBV"))
    )
    (comp (ref "U29")
      (value "SN6501 Transformer Drivers")
      (footprint "SOT23-5")
      (description "IC REG CONV PWR SUPPLIES SOT23-5")
      (fields (field (name "PART") "296-37700-1-ND"))
      (libsource (lib "Library_Microgrid") (part "SN6501"))
    )
    (comp (ref "U30")
      (value "TPS7A30")
      (footprint "8-TSSOP")
      (description "IC REG LDO NEG ADJ 0.2A 8MSOP")
      (fields (field (name "PART") "296-27750-1-ND"))
      (libsource (lib "Library_Microgrid") (part "TPS7A30"))
    )
  )
  (nets
    (net (code "1") (name "+5V_LV") (class "Default")
      (node (ref "C121") (pin "1") (pinfunction "OUT_1") (pintype "passive"))
      (node (ref "C123") (pin "1") (pinfunction "OUT_1") (pintype "passive"))
      (node (ref "C126") (pin "2") (pinfunction "OUT_2") (pintype "passive"))
      (node (ref "C127") (pin "2") (pinfunction "OUT_2") (pintype "passive"))
      (node (ref "C128") (pin "2") (pinfunction "OUT_2") (pintype "passive"))
      (node (ref "C146") (pin "1") (pinfunction "OUT_1") (pintype "passive"))
      (node (ref "C148") (pin "1") (pinfunction "OUT_1") (pintype "passive"))
      (node (ref "C151") (pin "2") (pinfunction "OUT_2") (pintype "passive"))
      (node (ref "C152") (pin "2") (pinfunction "OUT_2") (pintype "passive"))
      (node (ref "C153") (pin "2") (pinfunction "OUT_2") (pintype "passive"))
      (node (ref "C171") (pin "1") (pinfunction "OUT_1") (pintype "passive"))
      (node (ref "C173") (pin "1") (pinfunction "OUT_1") (pintype "passive"))
      (node (ref "C176") (pin "2") (pinfunction "OUT_2") (pintype "passive"))
      (node (ref "C177") (pin "2") (pinfunction "OUT_2") (pintype "passive"))
      (node (ref "C178") (pin "2") (pinfunction "OUT_2") (pintype "passive"))
      (node (ref "T5") (pin "2") (pinfunction "1_2") (pintype "passive"))
      (node (ref "T6") (pin "2") (pinfunction "1_2") (pintype "passive"))
      (node (ref "T7") (pin "2") (pinfunction "1_2") (pintype "passive"))
      (node (ref "U19") (pin "8") (pinfunction "V+_8") (pintype "passive"))
      (node (ref "U21") (pin "2") (pinfunction "VCC_2") (pintype "passive"))
      (node (ref "U23") (pin "8") (pinfunction "V+_8") (pintype "passive"))
      (node (ref "U25") (pin "2") (pinfunction "VCC_2") (pintype "passive"))
      (node (ref "U27") (pin "8") (pinfunction "V+_8") (pintype "passive"))
      (node (ref "U29") (pin "2") (pinfunction "VCC_2") (pintype "passive"))
    )
    (net (code "2") (name "+5V_USH2") (class "Default")
      (node (ref "C120") (pin "2") (pinfunction "OUT_2") (pintype "passive"))
      (node (ref "C122") (pin "2") (pinfunction "OUT_2") (pintype "passive"))
      (node (ref "C132") (pin "2") (pinfunction "OUT_2") (pintype "passive"))
      (node (ref "C133") (pin "2") (pinfunction "OUT_2") (pintype "passive"))
      (node (ref "D37") (pin "1") (pinfunction "Anode_1") (pintype "passive"))
      (node (ref "D38") (pin "1") (pinfunction "Anode_1") (pintype "passive"))
      (node (ref "D40") (pin "A") (pinfunction "A_A") (pintype "passive"))
      (node (ref "D41") (pin "1") (pinfunction "Anode_1") (pintype "passive"))
      (node (ref "FB20") (pin "2") (pinfunction "OUT_2") (pintype "passive"))
      (node (ref "R77") (pin "2") (pinfunction "A_2") (pintype "passive"))
      (node (ref "U19") (pin "1") (pinfunction "V+_1") (pintype "passive"))
    )
    (net (code "3") (name "+5V_VSH2") (class "Default")
      (node (ref "C145") (pin "2") (pinfunction "OUT_2") (pintype "passive"))
      (node (ref "C147") (pin "2") (pinfunction "OUT_2") (pintype "passive"))
      (node (ref "C157") (pin "2") (pinfunction "OUT_2") (pintype "passive"))
      (node (ref "C158") (pin "2") (pinfunction "OUT_2") (pintype "passive"))
      (node (ref "D45") (pin "1") (pinfunction "Anode_1") (pintype "passive"))
      (node (ref "D46") (pin "1") (pinfunction "Anode_1") (pintype "passive"))
      (node (ref "D48") (pin "A") (pinfunction "A_A") (pintype "passive"))
      (node (ref "D49") (pin "1") (pinfunction "Anode_1") (pintype "passive"))
      (node (ref "FB24") (pin "2") (pinfunction "OUT_2") (pintype "passive"))
      (node (ref "R86") (pin "2") (pinfunction "A_2") (pintype "passive"))
      (node (ref "U23") (pin "1") (pinfunction "V+_1") (pintype "passive"))
    )
    (net (code "4") (name "+5V_WSH2") (class "Default")
      (node (ref "C170") (pin "2") (pinfunction "OUT_2") (pintype "passive"))
      (node (ref "C172") (pin "2") (pinfunction "OUT_2") (pintype "passive"))
      (node (ref "C182") (pin "2") (pinfunction "OUT_2") (pintype "passive"))
      (node (ref "C183") (pin "2") (pinfunction "OUT_2") (pintype "passive"))
      (node (ref "D53") (pin "1") (pinfunction "Anode_1") (pintype "passive"))
      (node (ref "D54") (pin "1") (pinfunction "Anode_1") (pintype "passive"))
      (node (ref "D56") (pin "A") (pinfunction "A_A") (pintype "passive"))
      (node (ref "D57") (pin "1") (pinfunction "Anode_1") (pintype "passive"))
      (node (ref "FB28") (pin "2") (pinfunction "OUT_2") (pintype "passive"))
      (node (ref "R95") (pin "2") (pinfunction "A_2") (pintype "passive"))
      (node (ref "U27") (pin "1") (pinfunction "V+_1") (pintype "passive"))
    )
    (net (code "5") (name "+6V_USH2") (class "Default")
      (node (ref "C129") (pin "2") (pinfunction "OUT_2") (pintype "passive"))
      (node (ref "C130") (pin "2") (pinfunction "OUT_2") (pintype "passive"))
      (node (ref "C136") (pin "2") (pinfunction "OUT_2") (pintype "passive"))
      (node (ref "C137") (pin "2") (pinfunction "OUT_2") (pintype "passive"))
      (node (ref "D39") (pin "2") (pinfunction "Anode_2") (pintype "passive"))
      (node (ref "U20") (pin "2") (pinfunction "IN_2") (pintype "passive"))
    )
    (net (code "6") (name "+6V_VSH2") (class "Default")
      (node (ref "C154") (pin "2") (pinfunction "OUT_2") (pintype "passive"))
      (node (ref "C155") (pin "2") (pinfunction "OUT_2") (pintype "passive"))
      (node (ref "C161") (pin "2") (pinfunction "OUT_2") (pintype "passive"))
      (node (ref "C162") (pin "2") (pinfunction "OUT_2") (pintype "passive"))
      (node (ref "D47") (pin "2") (pinfunction "Anode_2") (pintype "passive"))
      (node (ref "U24") (pin "2") (pinfunction "IN_2") (pintype "passive"))
    )
    (net (code "7") (name "+6V_WSH2") (class "Default")
      (node (ref "C179") (pin "2") (pinfunction "OUT_2") (pintype "passive"))
      (node (ref "C180") (pin "2") (pinfunction "OUT_2") (pintype "passive"))
      (node (ref "C186") (pin "2") (pinfunction "OUT_2") (pintype "passive"))
      (node (ref "C187") (pin "2") (pinfunction "OUT_2") (pintype "passive"))
      (node (ref "D55") (pin "2") (pinfunction "Anode_2") (pintype "passive"))
      (node (ref "U28") (pin "2") (pinfunction "IN_2") (pintype "passive"))
    )
    (net (code "8") (name "-5V_USH2") (class "Default")
      (node (ref "C141") (pin "2") (pinfunction "OUT_2") (pintype "passive"))
      (node (ref "C142") (pin "2") (pinfunction "OUT_2") (pintype "passive"))
      (node (ref "D37") (pin "2") (pinfunction "Anode_2") (pintype "passive"))
      (node (ref "D38") (pin "2") (pinfunction "Anode_2") (pintype "passive"))
      (node (ref "D43") (pin "K") (pinfunction "K_K") (pintype "passive"))
      (node (ref "D44") (pin "2") (pinfunction "Anode_2") (pintype "passive"))
      (node (ref "FB21") (pin "2") (pinfunction "OUT_2") (pintype "passive"))
    )
    (net (code "9") (name "-5V_VSH2") (class "Default")
      (node (ref "C166") (pin "2") (pinfunction "OUT_2") (pintype "passive"))
      (node (ref "C167") (pin "2") (pinfunction "OUT_2") (pintype "passive"))
      (node (ref "D45") (pin "2") (pinfunction "Anode_2") (pintype "passive"))
      (node (ref "D46") (pin "2") (pinfunction "Anode_2") (pintype "passive"))
      (node (ref "D51") (pin "K") (pinfunction "K_K") (pintype "passive"))
      (node (ref "D52") (pin "2") (pinfunction "Anode_2") (pintype "passive"))
      (node (ref "FB25") (pin "2") (pinfunction "OUT_2") (pintype "passive"))
    )
    (net (code "10") (name "-5V_WSH2") (class "Default")
      (node (ref "C191") (pin "2") (pinfunction "OUT_2") (pintype "passive"))
      (node (ref "C192") (pin "2") (pinfunction "OUT_2") (pintype "passive"))
      (node (ref "D53") (pin "2") (pinfunction "Anode_2") (pintype "passive"))
      (node (ref "D54") (pin "2") (pinfunction "Anode_2") (pintype "passive"))
      (node (ref "D59") (pin "K") (pinfunction "K_K") (pintype "passive"))
      (node (ref "D60") (pin "2") (pinfunction "Anode_2") (pintype "passive"))
      (node (ref "FB29") (pin "2") (pinfunction "OUT_2") (pintype "passive"))
    )
    (net (code "11") (name "-6V_USH2") (class "Default")
      (node (ref "C134") (pin "1") (pinfunction "OUT_1") (pintype "passive"))
      (node (ref "C135") (pin "1") (pinfunction "OUT_1") (pintype "passive"))
      (node (ref "C138") (pin "2") (pinfunction "OUT_2") (pintype "passive"))
      (node (ref "C139") (pin "2") (pinfunction "OUT_2") (pintype "passive"))
      (node (ref "D42") (pin "1") (pinfunction "Anode_1") (pintype "passive"))
      (node (ref "U22") (pin "5") (pinfunction "EN_5") (pintype "passive"))
      (node (ref "U22") (pin "8") (pinfunction "VIN_8") (pintype "power_in"))
    )
    (net (code "12") (name "-6V_VSH2") (class "Default")
      (node (ref "C159") (pin "1") (pinfunction "OUT_1") (pintype "passive"))
      (node (ref "C160") (pin "1") (pinfunction "OUT_1") (pintype "passive"))
      (node (ref "C163") (pin "2") (pinfunction "OUT_2") (pintype "passive"))
      (node (ref "C164") (pin "2") (pinfunction "OUT_2") (pintype "passive"))
      (node (ref "D50") (pin "1") (pinfunction "Anode_1") (pintype "passive"))
      (node (ref "U26") (pin "5") (pinfunction "EN_5") (pintype "passive"))
      (node (ref "U26") (pin "8") (pinfunction "VIN_8") (pintype "power_in"))
    )
    (net (code "13") (name "-6V_WSH2") (class "Default")
      (node (ref "C184") (pin "1") (pinfunction "OUT_1") (pintype "passive"))
      (node (ref "C185") (pin "1") (pinfunction "OUT_1") (pintype "passive"))
      (node (ref "C188") (pin "2") (pinfunction "OUT_2") (pintype "passive"))
      (node (ref "C189") (pin "2") (pinfunction "OUT_2") (pintype "passive"))
      (node (ref "D58") (pin "1") (pinfunction "Anode_1") (pintype "passive"))
      (node (ref "U30") (pin "5") (pinfunction "EN_5") (pintype "passive"))
      (node (ref "U30") (pin "8") (pinfunction "VIN_8") (pintype "power_in"))
    )
    (net (code "14") (name "/IUP2") (class "Default")
      (node (ref "FB18") (pin "1") (pinfunction "OUT_1") (pintype "passive"))
    )
    (net (code "15") (name "/IVP2") (class "Default")
      (node (ref "FB22") (pin "1") (pinfunction "OUT_1") (pintype "passive"))
    )
    (net (code "16") (name "/IWP2") (class "Default")
      (node (ref "FB26") (pin "1") (pinfunction "OUT_1") (pintype "passive"))
    )
    (net (code "17") (name "/OUT_IUN2") (class "Default")
      (node (ref "R80") (pin "2") (pinfunction "A_2") (pintype "passive"))
    )
    (net (code "18") (name "/OUT_IUP2") (class "Default")
      (node (ref "R79") (pin "2") (pinfunction "A_2") (pintype "passive"))
    )
    (net (code "19") (name "/OUT_IVN2") (class "Default")
      (node (ref "R89") (pin "2") (pinfunction "A_2") (pintype "passive"))
    )
    (net (code "20") (name "/OUT_IVP2") (class "Default")
      (node (ref "R88") (pin "2") (pinfunction "A_2") (pintype "passive"))
    )
    (net (code "21") (name "/OUT_IWN2") (class "Default")
      (node (ref "R98") (pin "2") (pinfunction "A_2") (pintype "passive"))
    )
    (net (code "22") (name "/OUT_IWP2") (class "Default")
      (node (ref "R97") (pin "2") (pinfunction "A_2") (pintype "passive"))
    )
    (net (code "23") (name "GND_LV") (class "Default")
      (node (ref "C121") (pin "2") (pinfunction "OUT_2") (pintype "passive"))
      (node (ref "C123") (pin "2") (pinfunction "OUT_2") (pintype "passive"))
      (node (ref "C125") (pin "1") (pinfunction "1_1") (pintype "passive"))
      (node (ref "C126") (pin "1") (pinfunction "OUT_1") (pintype "passive"))
      (node (ref "C127") (pin "1") (pinfunction "OUT_1") (pintype "passive"))
      (node (ref "C128") (pin "1") (pinfunction "OUT_1") (pintype "passive"))
      (node (ref "C146") (pin "2") (pinfunction "OUT_2") (pintype "passive"))
      (node (ref "C148") (pin "2") (pinfunction "OUT_2") (pintype "passive"))
      (node (ref "C150") (pin "1") (pinfunction "1_1") (pintype "passive"))
      (node (ref "C151") (pin "1") (pinfunction "OUT_1") (pintype "passive"))
      (node (ref "C152") (pin "1") (pinfunction "OUT_1") (pintype "passive"))
      (node (ref "C153") (pin "1") (pinfunction "OUT_1") (pintype "passive"))
      (node (ref "C171") (pin "2") (pinfunction "OUT_2") (pintype "passive"))
      (node (ref "C173") (pin "2") (pinfunction "OUT_2") (pintype "passive"))
      (node (ref "C175") (pin "1") (pinfunction "1_1") (pintype "passive"))
      (node (ref "C176") (pin "1") (pinfunction "OUT_1") (pintype "passive"))
      (node (ref "C177") (pin "1") (pinfunction "OUT_1") (pintype "passive"))
      (node (ref "C178") (pin "1") (pinfunction "OUT_1") (pintype "passive"))
      (node (ref "U19") (pin "5") (pinfunction "V-_5") (pintype "passive"))
      (node (ref "U21") (pin "4") (pinfunction "GND_4") (pintype "passive"))
      (node (ref "U21") (pin "5") (pinfunction "GND_5") (pintype "passive"))
      (node (ref "U23") (pin "5") (pinfunction "V-_5") (pintype "passive"))
      (node (ref "U25") (pin "4") (pinfunction "GND_4") (pintype "passive"))
      (node (ref "U25") (pin "5") (pinfunction "GND_5") (pintype "passive"))
      (node (ref "U27") (pin "5") (pinfunction "V-_5") (pintype "passive"))
      (node (ref "U29") (pin "4") (pinfunction "GND_4") (pintype "passive"))
      (node (ref "U29") (pin "5") (pinfunction "GND_5") (pintype "passive"))
    )
    (net (code "24") (name "GND_USH2") (class "Default")
      (node (ref "C120") (pin "1") (pinfunction "OUT_1") (pintype "passive"))
      (node (ref "C122") (pin "1") (pinfunction "OUT_1") (pintype "passive"))
      (node (ref "C125") (pin "2") (pinfunction "2_2") (pintype "passive"))
      (node (ref "C129") (pin "1") (pinfunction "OUT_1") (pintype "passive"))
      (node (ref "C130") (pin "1") (pinfunction "OUT_1") (pintype "passive"))
      (node (ref "C131") (pin "1") (pinfunction "OUT_1") (pintype "passive"))
      (node (ref "C132") (pin "1") (pinfunction "OUT_1") (pintype "passive"))
      (node (ref "C133") (pin "1") (pinfunction "OUT_1") (pintype "passive"))
      (node (ref "C134") (pin "2") (pinfunction "OUT_2") (pintype "passive"))
      (node (ref "C135") (pin "2") (pinfunction "OUT_2") (pintype "passive"))
      (node (ref "C136") (pin "1") (pinfunction "OUT_1") (pintype "passive"))
      (node (ref "C137") (pin "1") (pinfunction "OUT_1") (pintype "passive"))
      (node (ref "C138") (pin "1") (pinfunction "OUT_1") (pintype "passive"))
      (node (ref "C139") (pin "1") (pinfunction "OUT_1") (pintype "passive"))
      (node (ref "C141") (pin "1") (pinfunction "OUT_1") (pintype "passive"))
      (node (ref "C142") (pin "1") (pinfunction "OUT_1") (pintype "passive"))
      (node (ref "C143") (pin "1") (pinfunction "OUT_1") (pintype "passive"))
      (node (ref "C144") (pin "1") (pinfunction "OUT_1") (pintype "passive"))
      (node (ref "D41") (pin "2") (pinfunction "Anode_2") (pintype "passive"))
      (node (ref "D44") (pin "1") (pinfunction "Anode_1") (pintype "passive"))
      (node (ref "FB19") (pin "1") (pinfunction "OUT_1") (pintype "passive"))
      (node (ref "R82") (pin "1") (pinfunction "A_1") (pintype "passive"))
      (node (ref "R84") (pin "1") (pinfunction "A_1") (pintype "passive"))
      (node (ref "R85") (pin "1") (pinfunction "A_1") (pintype "passive"))
      (node (ref "T5") (pin "4") (pinfunction "1_4") (pintype "passive"))
      (node (ref "U19") (pin "4") (pinfunction "V-_4") (pintype "passive"))
      (node (ref "U20") (pin "1") (pinfunction "GND_1") (pintype "passive"))
      (node (ref "U22") (pin "3") (pinfunction "NC_3") (pintype "passive"))
      (node (ref "U22") (pin "4") (pinfunction "GND_4") (pintype "power_in"))
      (node (ref "U22") (pin "9") (pinfunction "TPAD_9") (pintype "power_in"))
    )
    (net (code "25") (name "GND_VSH2") (class "Default")
      (node (ref "C145") (pin "1") (pinfunction "OUT_1") (pintype "passive"))
      (node (ref "C147") (pin "1") (pinfunction "OUT_1") (pintype "passive"))
      (node (ref "C150") (pin "2") (pinfunction "2_2") (pintype "passive"))
      (node (ref "C154") (pin "1") (pinfunction "OUT_1") (pintype "passive"))
      (node (ref "C155") (pin "1") (pinfunction "OUT_1") (pintype "passive"))
      (node (ref "C156") (pin "1") (pinfunction "OUT_1") (pintype "passive"))
      (node (ref "C157") (pin "1") (pinfunction "OUT_1") (pintype "passive"))
      (node (ref "C158") (pin "1") (pinfunction "OUT_1") (pintype "passive"))
      (node (ref "C159") (pin "2") (pinfunction "OUT_2") (pintype "passive"))
      (node (ref "C160") (pin "2") (pinfunction "OUT_2") (pintype "passive"))
      (node (ref "C161") (pin "1") (pinfunction "OUT_1") (pintype "passive"))
      (node (ref "C162") (pin "1") (pinfunction "OUT_1") (pintype "passive"))
      (node (ref "C163") (pin "1") (pinfunction "OUT_1") (pintype "passive"))
      (node (ref "C164") (pin "1") (pinfunction "OUT_1") (pintype "passive"))
      (node (ref "C166") (pin "1") (pinfunction "OUT_1") (pintype "passive"))
      (node (ref "C167") (pin "1") (pinfunction "OUT_1") (pintype "passive"))
      (node (ref "C168") (pin "1") (pinfunction "OUT_1") (pintype "passive"))
      (node (ref "C169") (pin "1") (pinfunction "OUT_1") (pintype "passive"))
      (node (ref "D49") (pin "2") (pinfunction "Anode_2") (pintype "passive"))
      (node (ref "D52") (pin "1") (pinfunction "Anode_1") (pintype "passive"))
      (node (ref "FB23") (pin "1") (pinfunction "OUT_1") (pintype "passive"))
      (node (ref "R91") (pin "1") (pinfunction "A_1") (pintype "passive"))
      (node (ref "R93") (pin "1") (pinfunction "A_1") (pintype "passive"))
      (node (ref "R94") (pin "1") (pinfunction "A_1") (pintype "passive"))
      (node (ref "T6") (pin "4") (pinfunction "1_4") (pintype "passive"))
      (node (ref "U23") (pin "4") (pinfunction "V-_4") (pintype "passive"))
      (node (ref "U24") (pin "1") (pinfunction "GND_1") (pintype "passive"))
      (node (ref "U26") (pin "3") (pinfunction "NC_3") (pintype "passive"))
      (node (ref "U26") (pin "4") (pinfunction "GND_4") (pintype "power_in"))
      (node (ref "U26") (pin "9") (pinfunction "TPAD_9") (pintype "power_in"))
    )
    (net (code "26") (name "GND_WSH2") (class "Default")
      (node (ref "C170") (pin "1") (pinfunction "OUT_1") (pintype "passive"))
      (node (ref "C172") (pin "1") (pinfunction "OUT_1") (pintype "passive"))
      (node (ref "C175") (pin "2") (pinfunction "2_2") (pintype "passive"))
      (node (ref "C179") (pin "1") (pinfunction "OUT_1") (pintype "passive"))
      (node (ref "C180") (pin "1") (pinfunction "OUT_1") (pintype "passive"))
      (node (ref "C181") (pin "1") (pinfunction "OUT_1") (pintype "passive"))
      (node (ref "C182") (pin "1") (pinfunction "OUT_1") (pintype "passive"))
      (node (ref "C183") (pin "1") (pinfunction "OUT_1") (pintype "passive"))
      (node (ref "C184") (pin "2") (pinfunction "OUT_2") (pintype "passive"))
      (node (ref "C185") (pin "2") (pinfunction "OUT_2") (pintype "passive"))
      (node (ref "C186") (pin "1") (pinfunction "OUT_1") (pintype "passive"))
      (node (ref "C187") (pin "1") (pinfunction "OUT_1") (pintype "passive"))
      (node (ref "C188") (pin "1") (pinfunction "OUT_1") (pintype "passive"))
      (node (ref "C189") (pin "1") (pinfunction "OUT_1") (pintype "passive"))
      (node (ref "C191") (pin "1") (pinfunction "OUT_1") (pintype "passive"))
      (node (ref "C192") (pin "1") (pinfunction "OUT_1") (pintype "passive"))
      (node (ref "C193") (pin "1") (pinfunction "OUT_1") (pintype "passive"))
      (node (ref "C194") (pin "1") (pinfunction "OUT_1") (pintype "passive"))
      (node (ref "D57") (pin "2") (pinfunction "Anode_2") (pintype "passive"))
      (node (ref "D60") (pin "1") (pinfunction "Anode_1") (pintype "passive"))
      (node (ref "FB27") (pin "1") (pinfunction "OUT_1") (pintype "passive"))
      (node (ref "R100") (pin "1") (pinfunction "A_1") (pintype "passive"))
      (node (ref "R102") (pin "1") (pinfunction "A_1") (pintype "passive"))
      (node (ref "R103") (pin "1") (pinfunction "A_1") (pintype "passive"))
      (node (ref "T7") (pin "4") (pinfunction "1_4") (pintype "passive"))
      (node (ref "U27") (pin "4") (pinfunction "V-_4") (pintype "passive"))
      (node (ref "U28") (pin "1") (pinfunction "GND_1") (pintype "passive"))
      (node (ref "U30") (pin "3") (pinfunction "NC_3") (pintype "passive"))
      (node (ref "U30") (pin "4") (pinfunction "GND_4") (pintype "power_in"))
      (node (ref "U30") (pin "9") (pinfunction "TPAD_9") (pintype "power_in"))
    )
    (net (code "27") (name "Net-(D37-Cathode)") (class "Default")
      (node (ref "C124") (pin "1") (pinfunction "OUT_1") (pintype "passive"))
      (node (ref "D37") (pin "C") (pinfunction "Cathode_C") (pintype "passive"))
      (node (ref "R77") (pin "1") (pinfunction "A_1") (pintype "passive"))
      (node (ref "R78") (pin "2") (pinfunction "A_2") (pintype "passive"))
      (node (ref "U19") (pin "2") (pinfunction "+_2") (pintype "passive"))
    )
    (net (code "28") (name "Net-(D38-Cathode)") (class "Default")
      (node (ref "C124") (pin "2") (pinfunction "OUT_2") (pintype "passive"))
      (node (ref "D38") (pin "C") (pinfunction "Cathode_C") (pintype "passive"))
      (node (ref "R81") (pin "2") (pinfunction "A_2") (pintype "passive"))
      (node (ref "U19") (pin "3") (pinfunction "-_3") (pintype "passive"))
    )
    (net (code "29") (name "Net-(D39-Anode-Pad1)") (class "Default")
      (node (ref "D39") (pin "1") (pinfunction "Anode_1") (pintype "passive"))
      (node (ref "D42") (pin "2") (pinfunction "Anode_2") (pintype "passive"))
      (node (ref "T5") (pin "6") (pinfunction "1_6") (pintype "passive"))
    )
    (net (code "30") (name "Net-(D40-PadK)") (class "Default")
      (node (ref "D40") (pin "K") (pinfunction "K_K") (pintype "passive"))
      (node (ref "R82") (pin "2") (pinfunction "A_2") (pintype "passive"))
    )
    (net (code "31") (name "Net-(D43-PadA)") (class "Default")
      (node (ref "D43") (pin "A") (pinfunction "A_A") (pintype "passive"))
      (node (ref "R84") (pin "2") (pinfunction "A_2") (pintype "passive"))
    )
    (net (code "32") (name "Net-(D45-Cathode)") (class "Default")
      (node (ref "C149") (pin "1") (pinfunction "OUT_1") (pintype "passive"))
      (node (ref "D45") (pin "C") (pinfunction "Cathode_C") (pintype "passive"))
      (node (ref "R86") (pin "1") (pinfunction "A_1") (pintype "passive"))
      (node (ref "R87") (pin "2") (pinfunction "A_2") (pintype "passive"))
      (node (ref "U23") (pin "2") (pinfunction "+_2") (pintype "passive"))
    )
    (net (code "33") (name "Net-(D46-Cathode)") (class "Default")
      (node (ref "C149") (pin "2") (pinfunction "OUT_2") (pintype "passive"))
      (node (ref "D46") (pin "C") (pinfunction "Cathode_C") (pintype "passive"))
      (node (ref "R90") (pin "2") (pinfunction "A_2") (pintype "passive"))
      (node (ref "U23") (pin "3") (pinfunction "-_3") (pintype "passive"))
    )
    (net (code "34") (name "Net-(D47-Anode-Pad1)") (class "Default")
      (node (ref "D47") (pin "1") (pinfunction "Anode_1") (pintype "passive"))
      (node (ref "D50") (pin "2") (pinfunction "Anode_2") (pintype "passive"))
      (node (ref "T6") (pin "6") (pinfunction "1_6") (pintype "passive"))
    )
    (net (code "35") (name "Net-(D48-PadK)") (class "Default")
      (node (ref "D48") (pin "K") (pinfunction "K_K") (pintype "passive"))
      (node (ref "R91") (pin "2") (pinfunction "A_2") (pintype "passive"))
    )
    (net (code "36") (name "Net-(D51-PadA)") (class "Default")
      (node (ref "D51") (pin "A") (pinfunction "A_A") (pintype "passive"))
      (node (ref "R93") (pin "2") (pinfunction "A_2") (pintype "passive"))
    )
    (net (code "37") (name "Net-(D53-Cathode)") (class "Default")
      (node (ref "C174") (pin "1") (pinfunction "OUT_1") (pintype "passive"))
      (node (ref "D53") (pin "C") (pinfunction "Cathode_C") (pintype "passive"))
      (node (ref "R95") (pin "1") (pinfunction "A_1") (pintype "passive"))
      (node (ref "R96") (pin "2") (pinfunction "A_2") (pintype "passive"))
      (node (ref "U27") (pin "2") (pinfunction "+_2") (pintype "passive"))
    )
    (net (code "38") (name "Net-(D54-Cathode)") (class "Default")
      (node (ref "C174") (pin "2") (pinfunction "OUT_2") (pintype "passive"))
      (node (ref "D54") (pin "C") (pinfunction "Cathode_C") (pintype "passive"))
      (node (ref "R99") (pin "2") (pinfunction "A_2") (pintype "passive"))
      (node (ref "U27") (pin "3") (pinfunction "-_3") (pintype "passive"))
    )
    (net (code "39") (name "Net-(D55-Anode-Pad1)") (class "Default")
      (node (ref "D55") (pin "1") (pinfunction "Anode_1") (pintype "passive"))
      (node (ref "D58") (pin "2") (pinfunction "Anode_2") (pintype "passive"))
      (node (ref "T7") (pin "6") (pinfunction "1_6") (pintype "passive"))
    )
    (net (code "40") (name "Net-(D56-PadK)") (class "Default")
      (node (ref "D56") (pin "K") (pinfunction "K_K") (pintype "passive"))
      (node (ref "R100") (pin "2") (pinfunction "A_2") (pintype "passive"))
    )
    (net (code "41") (name "Net-(D59-PadA)") (class "Default")
      (node (ref "D59") (pin "A") (pinfunction "A_A") (pintype "passive"))
      (node (ref "R102") (pin "2") (pinfunction "A_2") (pintype "passive"))
    )
    (net (code "42") (name "Net-(FB18-OUT-Pad2)") (class "Default")
      (node (ref "FB18") (pin "2") (pinfunction "OUT_2") (pintype "passive"))
      (node (ref "R78") (pin "1") (pinfunction "A_1") (pintype "passive"))
    )
    (net (code "43") (name "Net-(FB19-OUT-Pad2)") (class "Default")
      (node (ref "FB19") (pin "2") (pinfunction "OUT_2") (pintype "passive"))
      (node (ref "R81") (pin "1") (pinfunction "A_1") (pintype "passive"))
    )
    (net (code "44") (name "Net-(FB22-OUT-Pad2)") (class "Default")
      (node (ref "FB22") (pin "2") (pinfunction "OUT_2") (pintype "passive"))
      (node (ref "R87") (pin "1") (pinfunction "A_1") (pintype "passive"))
    )
    (net (code "45") (name "Net-(FB23-OUT-Pad2)") (class "Default")
      (node (ref "FB23") (pin "2") (pinfunction "OUT_2") (pintype "passive"))
      (node (ref "R90") (pin "1") (pinfunction "A_1") (pintype "passive"))
    )
    (net (code "46") (name "Net-(FB26-OUT-Pad2)") (class "Default")
      (node (ref "FB26") (pin "2") (pinfunction "OUT_2") (pintype "passive"))
      (node (ref "R96") (pin "1") (pinfunction "A_1") (pintype "passive"))
    )
    (net (code "47") (name "Net-(FB27-OUT-Pad2)") (class "Default")
      (node (ref "FB27") (pin "2") (pinfunction "OUT_2") (pintype "passive"))
      (node (ref "R99") (pin "1") (pinfunction "A_1") (pintype "passive"))
    )
    (net (code "48") (name "Net-(R79-A-Pad1)") (class "Default")
      (node (ref "R79") (pin "1") (pinfunction "A_1") (pintype "passive"))
      (node (ref "U19") (pin "7") (pinfunction "+_7") (pintype "passive"))
    )
    (net (code "49") (name "Net-(R80-A-Pad1)") (class "Default")
      (node (ref "R80") (pin "1") (pinfunction "A_1") (pintype "passive"))
      (node (ref "U19") (pin "6") (pinfunction "-_6") (pintype "passive"))
    )
    (net (code "50") (name "Net-(R88-A-Pad1)") (class "Default")
      (node (ref "R88") (pin "1") (pinfunction "A_1") (pintype "passive"))
      (node (ref "U23") (pin "7") (pinfunction "+_7") (pintype "passive"))
    )
    (net (code "51") (name "Net-(R89-A-Pad1)") (class "Default")
      (node (ref "R89") (pin "1") (pinfunction "A_1") (pintype "passive"))
      (node (ref "U23") (pin "6") (pinfunction "-_6") (pintype "passive"))
    )
    (net (code "52") (name "Net-(R97-A-Pad1)") (class "Default")
      (node (ref "R97") (pin "1") (pinfunction "A_1") (pintype "passive"))
      (node (ref "U27") (pin "7") (pinfunction "+_7") (pintype "passive"))
    )
    (net (code "53") (name "Net-(R98-A-Pad1)") (class "Default")
      (node (ref "R98") (pin "1") (pinfunction "A_1") (pintype "passive"))
      (node (ref "U27") (pin "6") (pinfunction "-_6") (pintype "passive"))
    )
    (net (code "54") (name "Net-(U20-OUT)") (class "Default")
      (node (ref "C131") (pin "2") (pinfunction "OUT_2") (pintype "passive"))
      (node (ref "FB20") (pin "1") (pinfunction "OUT_1") (pintype "passive"))
      (node (ref "U20") (pin "3") (pinfunction "OUT_3") (pintype "passive"))
    )
    (net (code "55") (name "Net-(U21-D1)") (class "Default")
      (node (ref "T5") (pin "3") (pinfunction "1_3") (pintype "passive"))
      (node (ref "U21") (pin "1") (pinfunction "D1_1") (pintype "passive"))
    )
    (net (code "56") (name "Net-(U21-D2)") (class "Default")
      (node (ref "T5") (pin "1") (pinfunction "1_1") (pintype "passive"))
      (node (ref "U21") (pin "3") (pinfunction "D2_3") (pintype "passive"))
    )
    (net (code "57") (name "Net-(U22-FB)") (class "Default")
      (node (ref "C140") (pin "2") (pinfunction "OUT_2") (pintype "passive"))
      (node (ref "R83") (pin "1") (pinfunction "A_1") (pintype "passive"))
      (node (ref "R85") (pin "2") (pinfunction "A_2") (pintype "passive"))
      (node (ref "U22") (pin "2") (pinfunction "FB_2") (pintype "passive"))
    )
    (net (code "58") (name "Net-(U22-NR{slash}SS)") (class "Default")
      (node (ref "C144") (pin "2") (pinfunction "OUT_2") (pintype "passive"))
      (node (ref "U22") (pin "6") (pinfunction "NR/SS_6") (pintype "power_in"))
    )
    (net (code "59") (name "Net-(U22-OUT)") (class "Default")
      (node (ref "C140") (pin "1") (pinfunction "OUT_1") (pintype "passive"))
      (node (ref "C143") (pin "2") (pinfunction "OUT_2") (pintype "passive"))
      (node (ref "FB21") (pin "1") (pinfunction "OUT_1") (pintype "passive"))
      (node (ref "R83") (pin "2") (pinfunction "A_2") (pintype "passive"))
      (node (ref "U22") (pin "1") (pinfunction "OUT_1") (pintype "passive"))
    )
    (net (code "60") (name "Net-(U24-OUT)") (class "Default")
      (node (ref "C156") (pin "2") (pinfunction "OUT_2") (pintype "passive"))
      (node (ref "FB24") (pin "1") (pinfunction "OUT_1") (pintype "passive"))
      (node (ref "U24") (pin "3") (pinfunction "OUT_3") (pintype "passive"))
    )
    (net (code "61") (name "Net-(U25-D1)") (class "Default")
      (node (ref "T6") (pin "3") (pinfunction "1_3") (pintype "passive"))
      (node (ref "U25") (pin "1") (pinfunction "D1_1") (pintype "passive"))
    )
    (net (code "62") (name "Net-(U25-D2)") (class "Default")
      (node (ref "T6") (pin "1") (pinfunction "1_1") (pintype "passive"))
      (node (ref "U25") (pin "3") (pinfunction "D2_3") (pintype "passive"))
    )
    (net (code "63") (name "Net-(U26-FB)") (class "Default")
      (node (ref "C165") (pin "2") (pinfunction "OUT_2") (pintype "passive"))
      (node (ref "R92") (pin "1") (pinfunction "A_1") (pintype "passive"))
      (node (ref "R94") (pin "2") (pinfunction "A_2") (pintype "passive"))
      (node (ref "U26") (pin "2") (pinfunction "FB_2") (pintype "passive"))
    )
    (net (code "64") (name "Net-(U26-NR{slash}SS)") (class "Default")
      (node (ref "C169") (pin "2") (pinfunction "OUT_2") (pintype "passive"))
      (node (ref "U26") (pin "6") (pinfunction "NR/SS_6") (pintype "power_in"))
    )
    (net (code "65") (name "Net-(U26-OUT)") (class "Default")
      (node (ref "C165") (pin "1") (pinfunction "OUT_1") (pintype "passive"))
      (node (ref "C168") (pin "2") (pinfunction "OUT_2") (pintype "passive"))
      (node (ref "FB25") (pin "1") (pinfunction "OUT_1") (pintype "passive"))
      (node (ref "R92") (pin "2") (pinfunction "A_2") (pintype "passive"))
      (node (ref "U26") (pin "1") (pinfunction "OUT_1") (pintype "passive"))
    )
    (net (code "66") (name "Net-(U28-OUT)") (class "Default")
      (node (ref "C181") (pin "2") (pinfunction "OUT_2") (pintype "passive"))
      (node (ref "FB28") (pin "1") (pinfunction "OUT_1") (pintype "passive"))
      (node (ref "U28") (pin "3") (pinfunction "OUT_3") (pintype "passive"))
    )
    (net (code "67") (name "Net-(U29-D1)") (class "Default")
      (node (ref "T7") (pin "3") (pinfunction "1_3") (pintype "passive"))
      (node (ref "U29") (pin "1") (pinfunction "D1_1") (pintype "passive"))
    )
    (net (code "68") (name "Net-(U29-D2)") (class "Default")
      (node (ref "T7") (pin "1") (pinfunction "1_1") (pintype "passive"))
      (node (ref "U29") (pin "3") (pinfunction "D2_3") (pintype "passive"))
    )
    (net (code "69") (name "Net-(U30-FB)") (class "Default")
      (node (ref "C190") (pin "2") (pinfunction "OUT_2") (pintype "passive"))
      (node (ref "R101") (pin "1") (pinfunction "A_1") (pintype "passive"))
      (node (ref "R103") (pin "2") (pinfunction "A_2") (pintype "passive"))
      (node (ref "U30") (pin "2") (pinfunction "FB_2") (pintype "passive"))
    )
    (net (code "70") (name "Net-(U30-NR{slash}SS)") (class "Default")
      (node (ref "C194") (pin "2") (pinfunction "OUT_2") (pintype "passive"))
      (node (ref "U30") (pin "6") (pinfunction "NR/SS_6") (pintype "power_in"))
    )
    (net (code "71") (name "Net-(U30-OUT)") (class "Default")
      (node (ref "C190") (pin "1") (pinfunction "OUT_1") (pintype "passive"))
      (node (ref "C193") (pin "2") (pinfunction "OUT_2") (pintype "passive"))
      (node (ref "FB29") (pin "1") (pinfunction "OUT_1") (pintype "passive"))
      (node (ref "R101") (pin "2") (pinfunction "A_2") (pintype "passive"))
      (node (ref "U30") (pin "1") (pinfunction "OUT_1") (pintype "passive"))
    )
    (net (code "72") (name "unconnected-(T5-1-Pad5)") (class "Default")
      (node (ref "T5") (pin "5") (pinfunction "1_5") (pintype "passive"))
    )
    (net (code "73") (name "unconnected-(T6-1-Pad5)") (class "Default")
      (node (ref "T6") (pin "5") (pinfunction "1_5") (pintype "passive"))
    )
    (net (code "74") (name "unconnected-(T7-1-Pad5)") (class "Default")
      (node (ref "T7") (pin "5") (pinfunction "1_5") (pintype "passive"))
    )
    (net (code "75") (name "unconnected-(U20-NC-Pad4)") (class "Default")
      (node (ref "U20") (pin "4") (pinfunction "NC_4") (pintype "passive"))
    )
    (net (code "76") (name "unconnected-(U20-NC-Pad5)") (class "Default")
      (node (ref "U20") (pin "5") (pinfunction "NC_5") (pintype "passive"))
    )
    (net (code "77") (name "unconnected-(U22-DNC-Pad7)") (class "Default")
      (node (ref "U22") (pin "7") (pinfunction "DNC_7") (pintype "passive"))
    )
    (net (code "78") (name "unconnected-(U24-NC-Pad4)") (class "Default")
      (node (ref "U24") (pin "4") (pinfunction "NC_4") (pintype "passive"))
    )
    (net (code "79") (name "unconnected-(U24-NC-Pad5)") (class "Default")
      (node (ref "U24") (pin "5") (pinfunction "NC_5") (pintype "passive"))
    )
    (net (code "80") (name "unconnected-(U26-DNC-Pad7)") (class "Default")
      (node (ref "U26") (pin "7") (pinfunction "DNC_7") (pintype "passive"))
    )
    (net (code "81") (name "unconnected-(U28-NC-Pad4)") (class "Default")
      (node (ref "U28") (pin "4") (pinfunction "NC_4") (pintype "passive"))
    )
    (net (code "82") (name "unconnected-(U28-NC-Pad5)") (class "Default")
      (node (ref "U28") (pin "5") (pinfunction "NC_5") (pintype "passive"))
    )
    (net (code "83") (name "unconnected-(U30-DNC-Pad7)") (class "Default")
      (node (ref "U30") (pin "7") (pinfunction "DNC_7") (pintype "passive"))
    )
  )
)
